# axiom_beta_sensor_cmv12000_tht_v0_16c.net
KiCad netlist of a schematic drawn in EAGLE
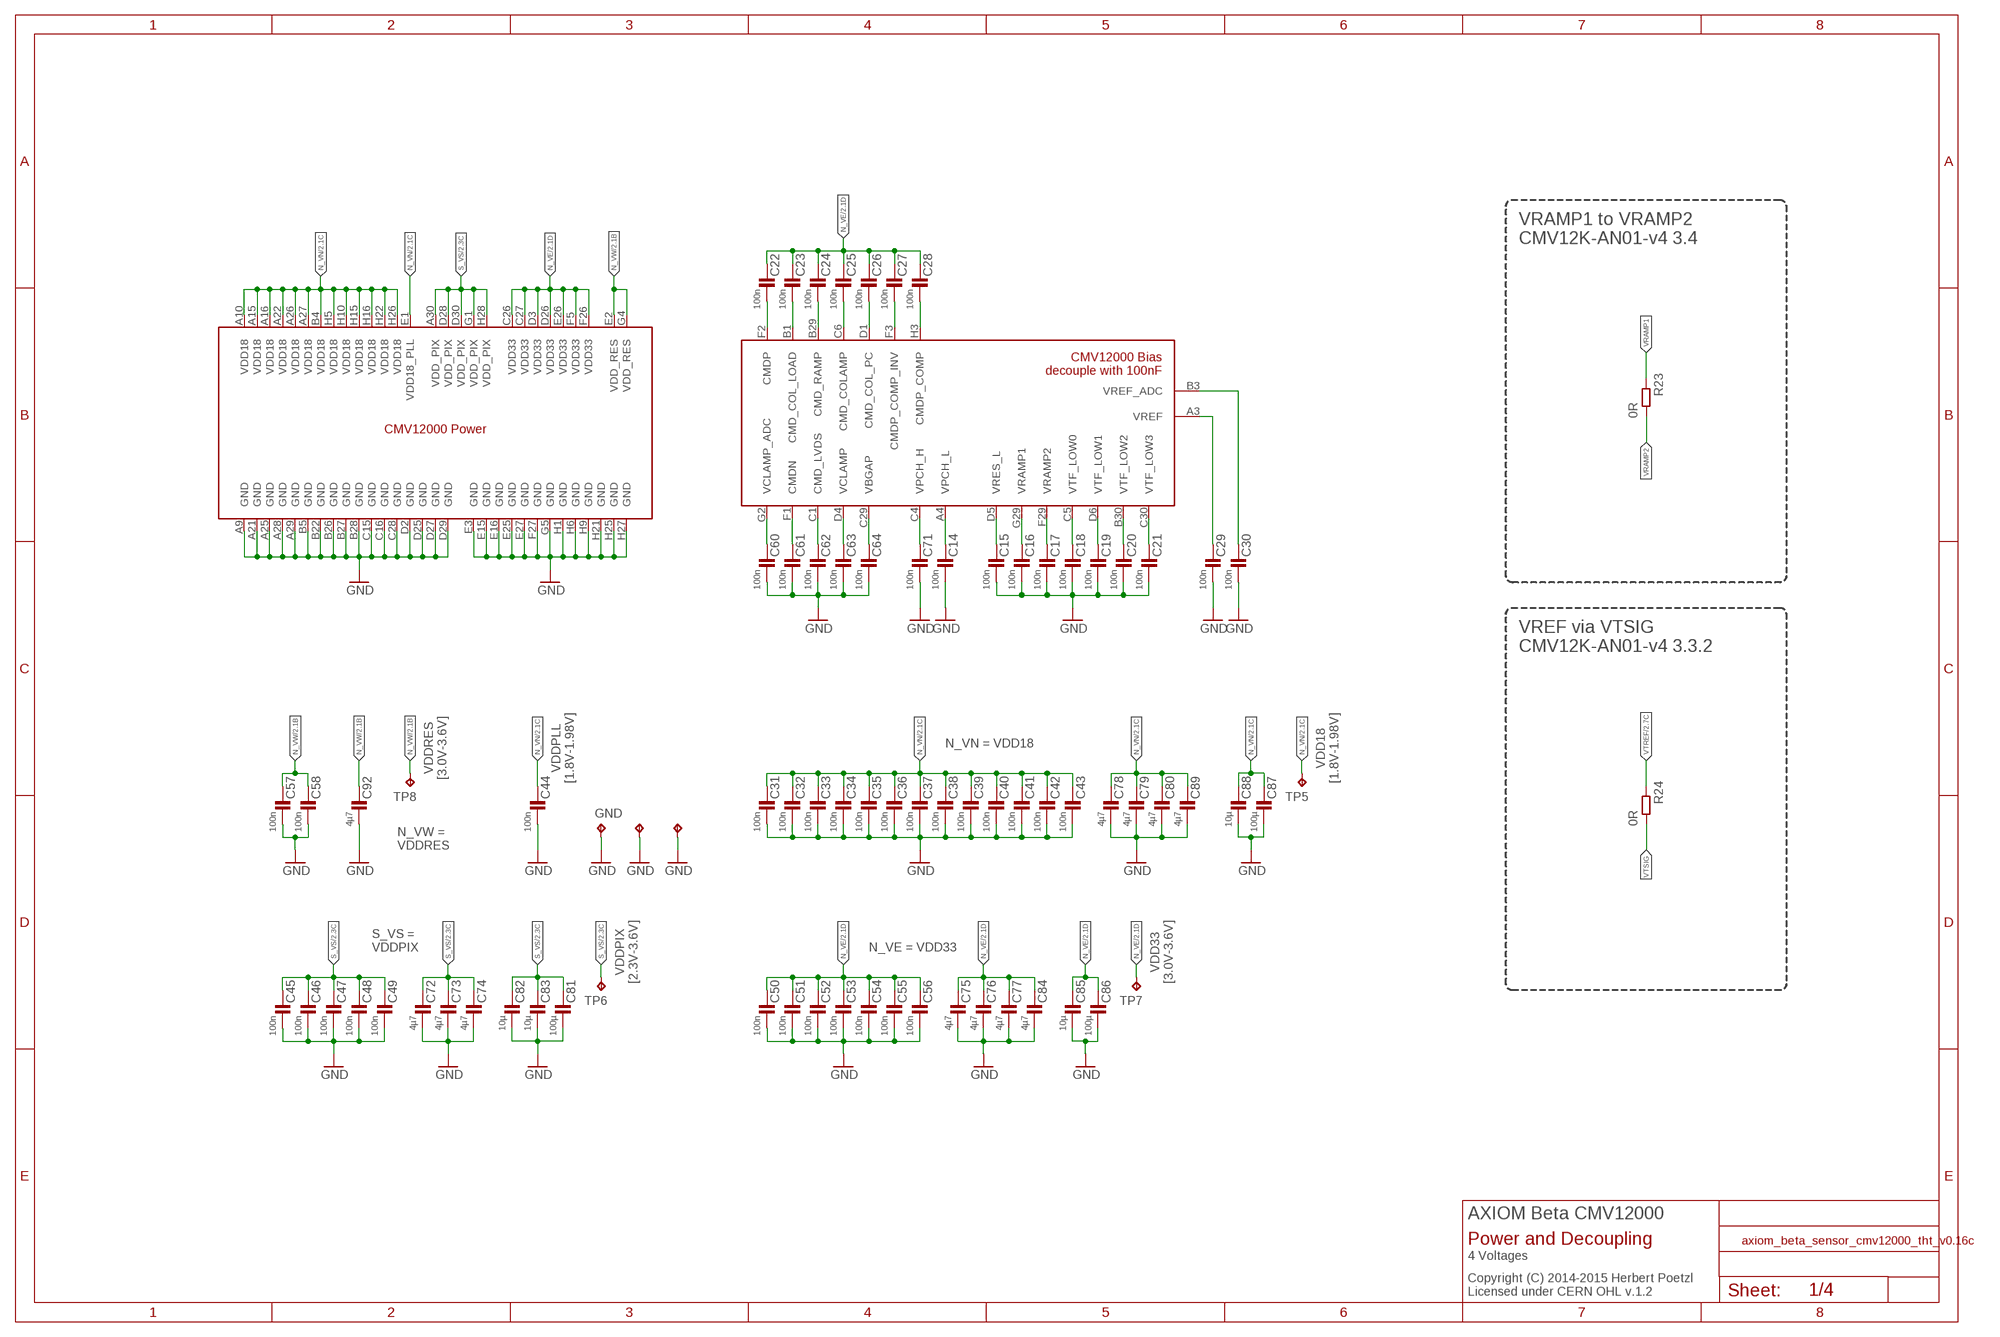
[diagram p0: schematic, sheet 1]
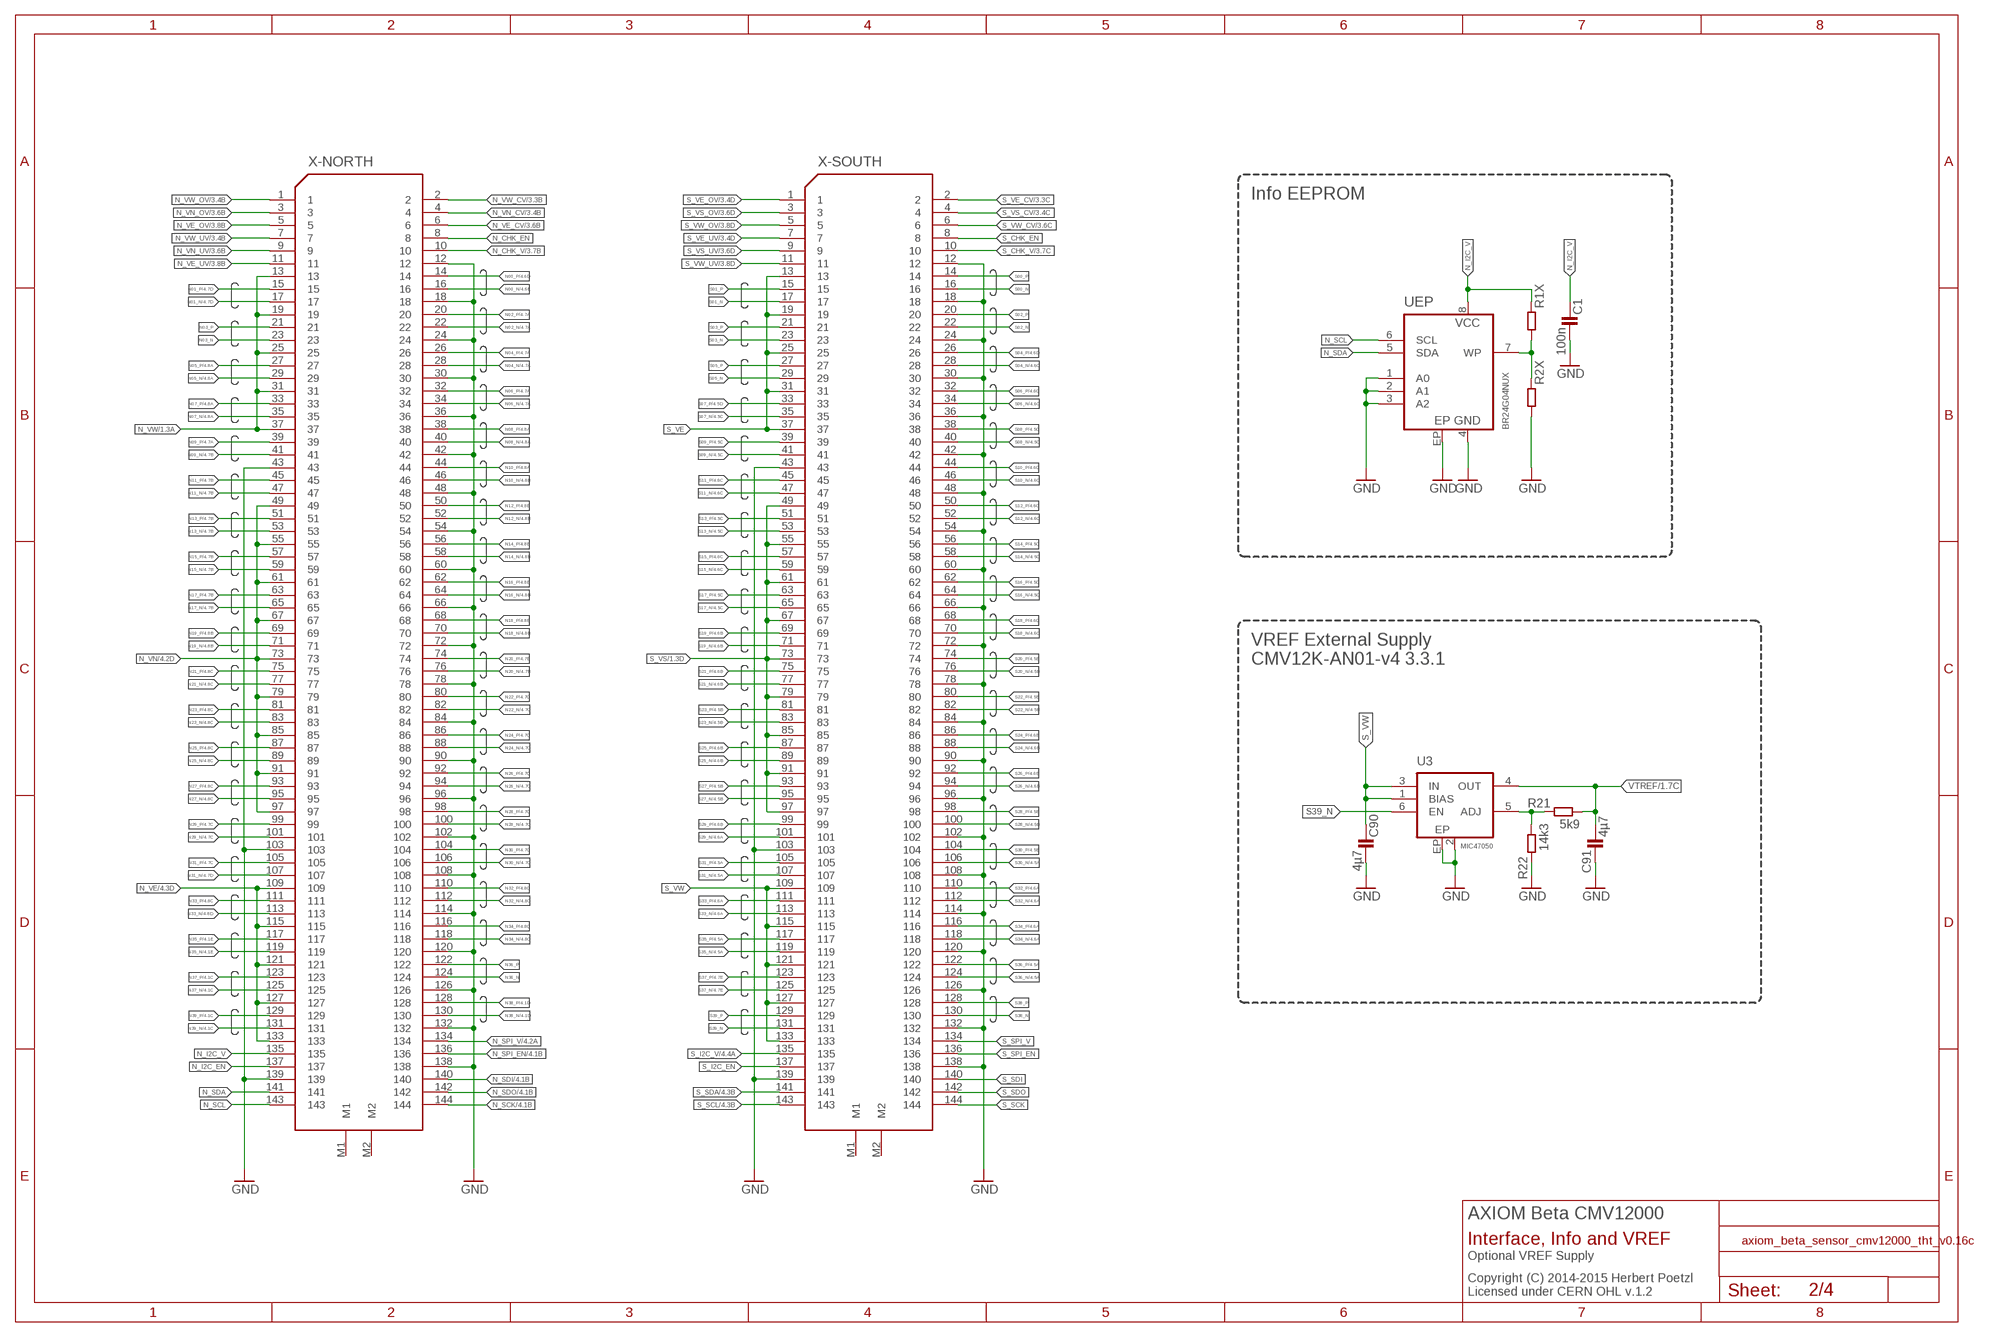
[diagram p1: schematic, sheet 2]
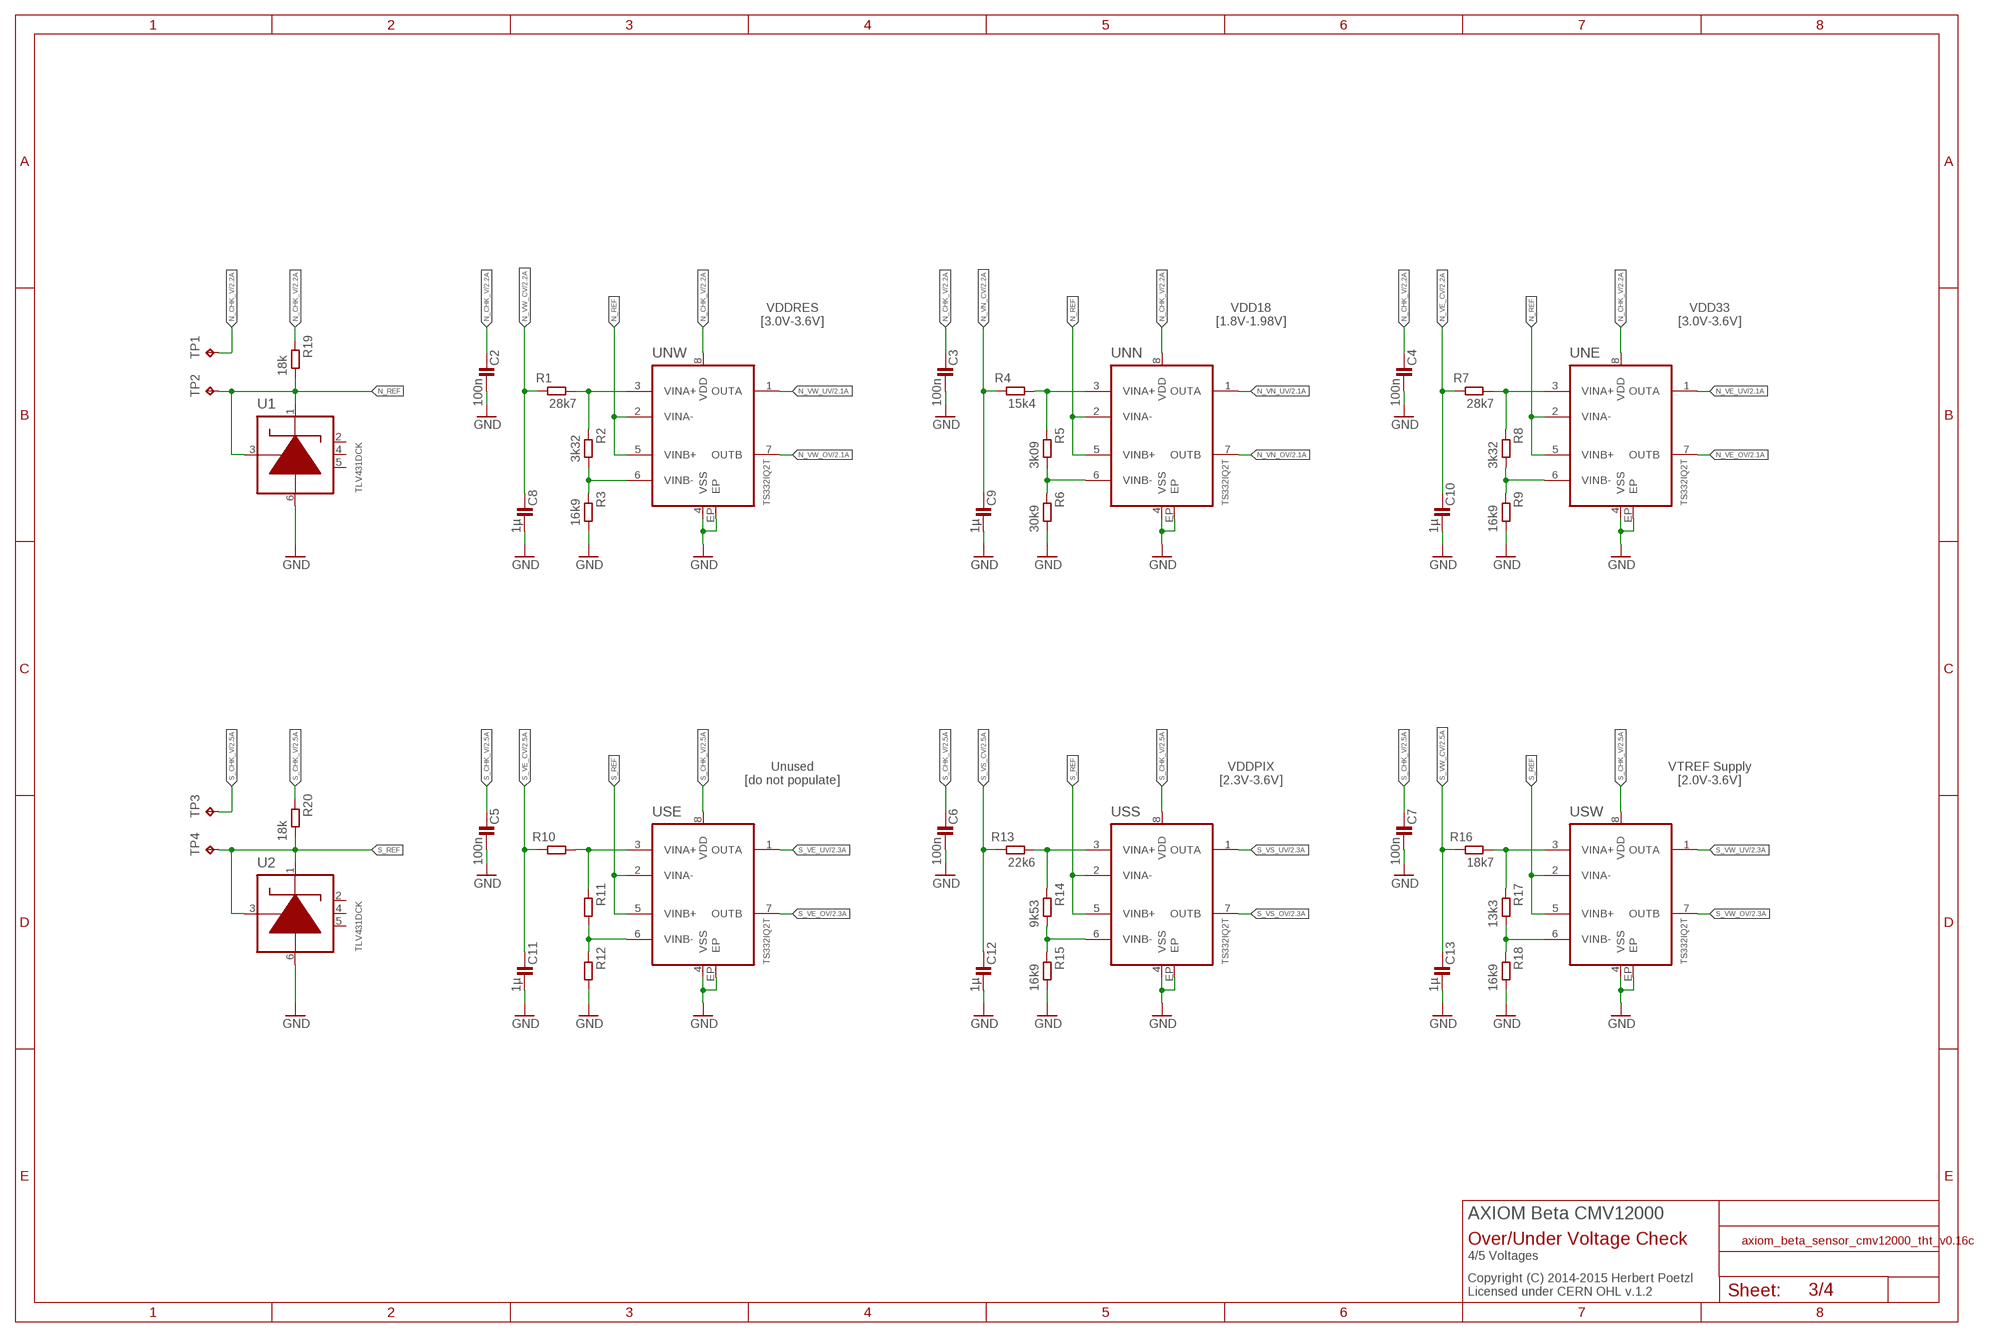
[diagram p2: schematic, sheet 3]
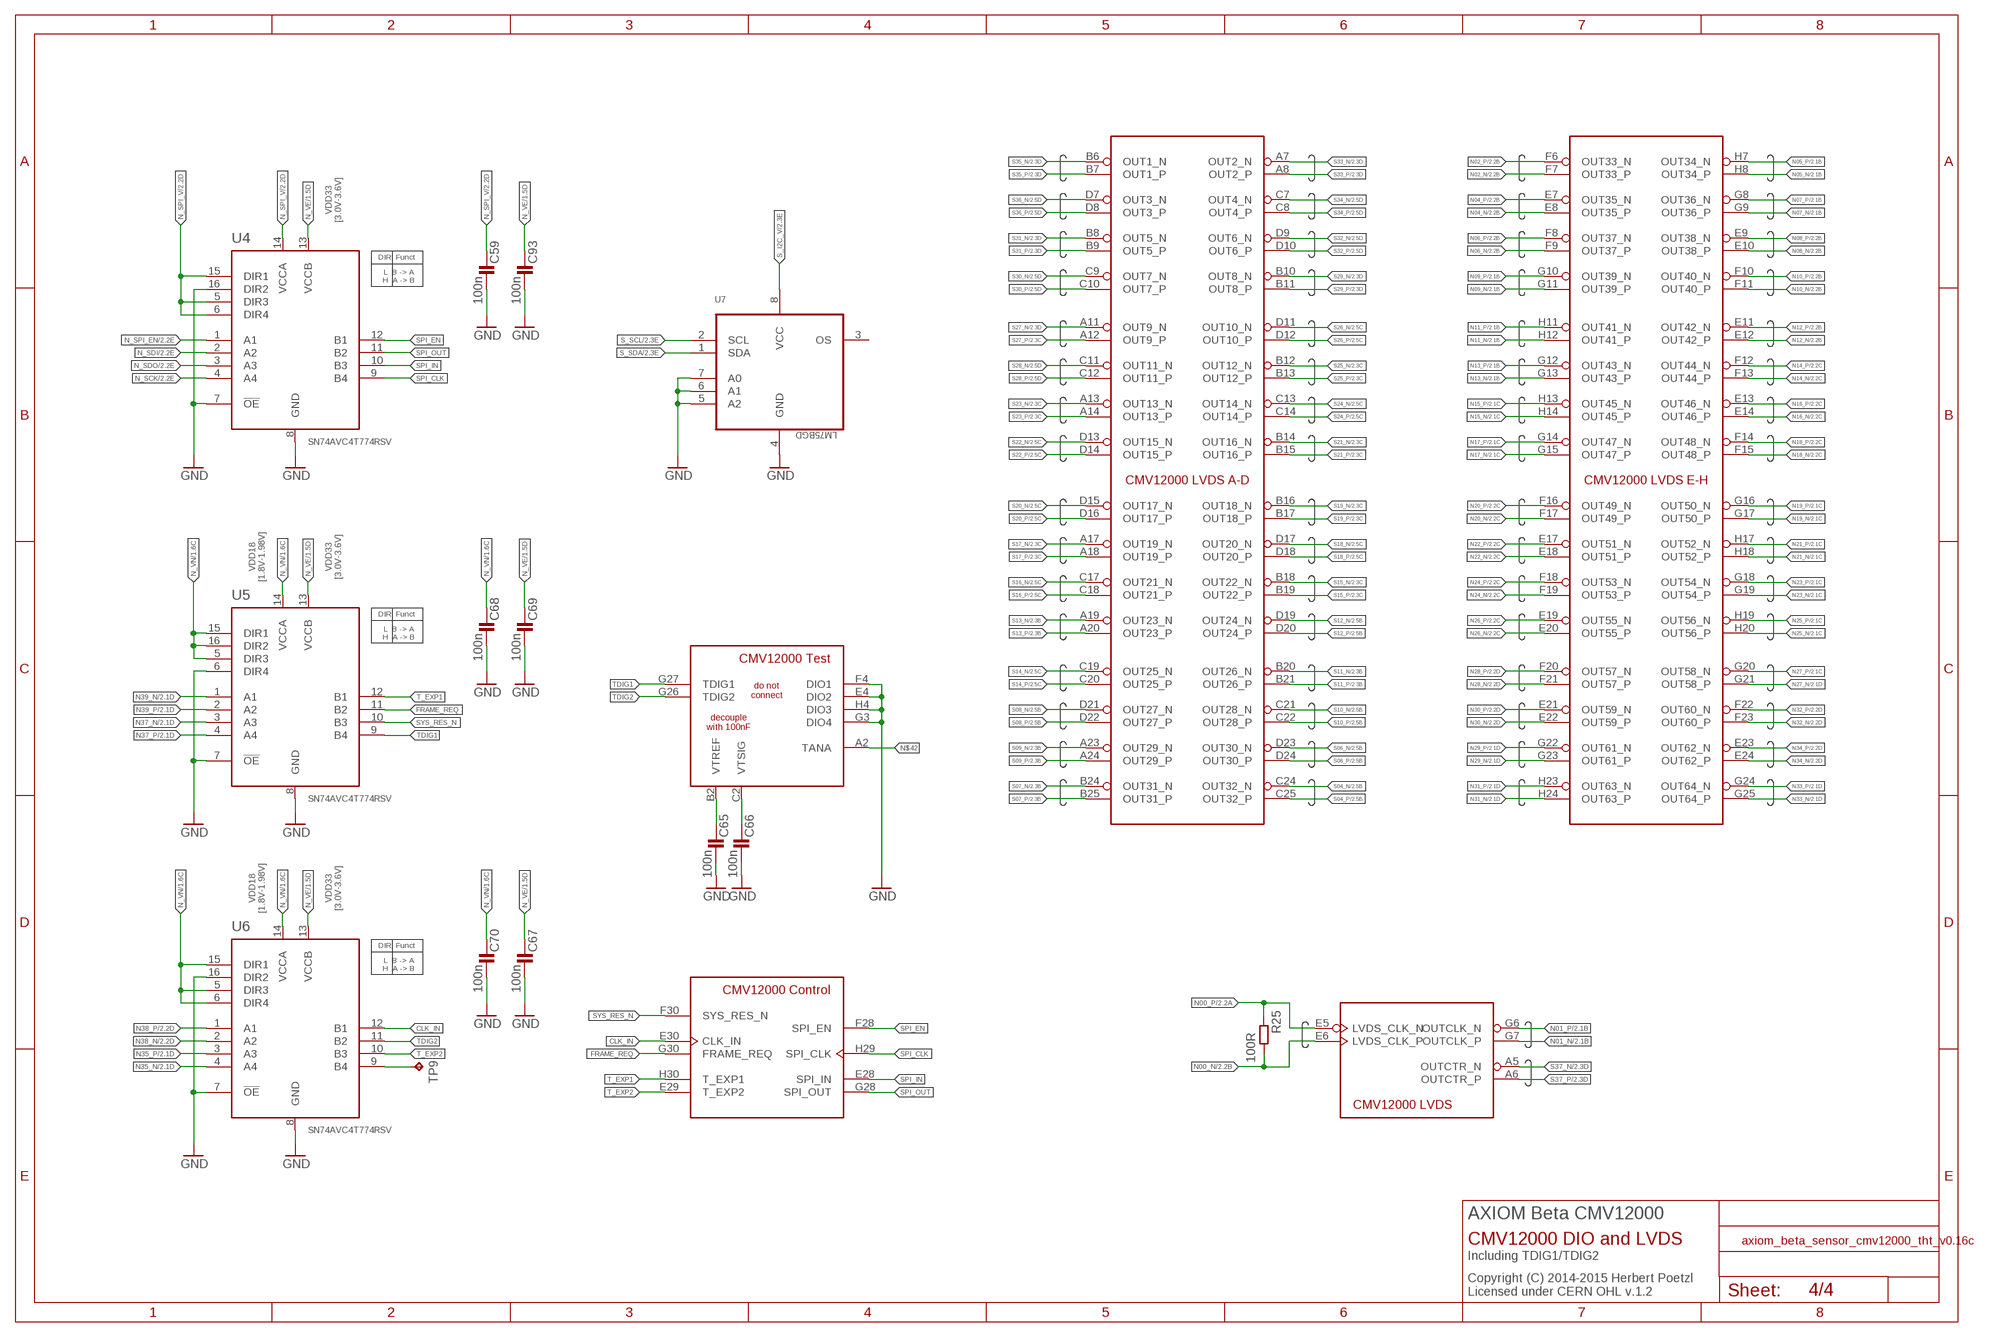
[diagram p3: schematic, sheet 4]

(export (version "E")
  (design (tool "Eeschema 10.0.6"))
  (components
    (comp (ref "C2")
      (value "100n")
      (footprint "eagle-import:0402-C")
      (libsource (lib "eagle-import") (part "C0402-C"))
    )
    (comp (ref "C3")
      (value "100n")
      (footprint "eagle-import:0402-C")
      (libsource (lib "eagle-import") (part "C0402-C"))
    )
    (comp (ref "C4")
      (value "100n")
      (footprint "eagle-import:0402-C")
      (libsource (lib "eagle-import") (part "C0402-C"))
    )
    (comp (ref "C5")
      (value "100n")
      (footprint "eagle-import:0402-C")
      (libsource (lib "eagle-import") (part "C0402-C"))
    )
    (comp (ref "C6")
      (value "100n")
      (footprint "eagle-import:0402-C")
      (libsource (lib "eagle-import") (part "C0402-C"))
    )
    (comp (ref "C7")
      (value "100n")
      (footprint "eagle-import:0402-C")
      (libsource (lib "eagle-import") (part "C0402-C"))
    )
    (comp (ref "C8")
      (value "1µ")
      (footprint "eagle-import:0402-C")
      (libsource (lib "eagle-import") (part "C0402-C"))
    )
    (comp (ref "C9")
      (value "1µ")
      (footprint "eagle-import:0402-C")
      (libsource (lib "eagle-import") (part "C0402-C"))
    )
    (comp (ref "C10")
      (value "1µ")
      (footprint "eagle-import:0402-C")
      (libsource (lib "eagle-import") (part "C0402-C"))
    )
    (comp (ref "C11")
      (value "1µ")
      (footprint "eagle-import:0402-C")
      (libsource (lib "eagle-import") (part "C0402-C"))
    )
    (comp (ref "C12")
      (value "1µ")
      (footprint "eagle-import:0402-C")
      (libsource (lib "eagle-import") (part "C0402-C"))
    )
    (comp (ref "C13")
      (value "1µ")
      (footprint "eagle-import:0402-C")
      (libsource (lib "eagle-import") (part "C0402-C"))
    )
    (comp (ref "R1")
      (value "28k7")
      (footprint "eagle-import:0402-C")
      (libsource (lib "eagle-import") (part "R0402-C"))
    )
    (comp (ref "R2")
      (value "3k32")
      (footprint "eagle-import:0402-C")
      (libsource (lib "eagle-import") (part "R0402-C"))
    )
    (comp (ref "R3")
      (value "16k9")
      (footprint "eagle-import:0402-C")
      (libsource (lib "eagle-import") (part "R0402-C"))
    )
    (comp (ref "R4")
      (value "15k4")
      (footprint "eagle-import:0402-C")
      (libsource (lib "eagle-import") (part "R0402-C"))
    )
    (comp (ref "R5")
      (value "3k09")
      (footprint "eagle-import:0402-C")
      (libsource (lib "eagle-import") (part "R0402-C"))
    )
    (comp (ref "R6")
      (value "30k9")
      (footprint "eagle-import:0402-C")
      (libsource (lib "eagle-import") (part "R0402-C"))
    )
    (comp (ref "R7")
      (value "28k7")
      (footprint "eagle-import:0402-C")
      (libsource (lib "eagle-import") (part "R0402-C"))
    )
    (comp (ref "R8")
      (value "3k32")
      (footprint "eagle-import:0402-C")
      (libsource (lib "eagle-import") (part "R0402-C"))
    )
    (comp (ref "R9")
      (value "16k9")
      (footprint "eagle-import:0402-C")
      (libsource (lib "eagle-import") (part "R0402-C"))
    )
    (comp (ref "R10")
      (value "R0402-C")
      (footprint "eagle-import:0402-C")
      (libsource (lib "eagle-import") (part "R0402-C"))
    )
    (comp (ref "R11")
      (value "R0402-C")
      (footprint "eagle-import:0402-C")
      (libsource (lib "eagle-import") (part "R0402-C"))
    )
    (comp (ref "R12")
      (value "R0402-C")
      (footprint "eagle-import:0402-C")
      (libsource (lib "eagle-import") (part "R0402-C"))
    )
    (comp (ref "R13")
      (value "22k6")
      (footprint "eagle-import:0402-C")
      (libsource (lib "eagle-import") (part "R0402-C"))
    )
    (comp (ref "R14")
      (value "9k53")
      (footprint "eagle-import:0402-C")
      (libsource (lib "eagle-import") (part "R0402-C"))
    )
    (comp (ref "R15")
      (value "16k9")
      (footprint "eagle-import:0402-C")
      (libsource (lib "eagle-import") (part "R0402-C"))
    )
    (comp (ref "R16")
      (value "18k7")
      (footprint "eagle-import:0402-C")
      (libsource (lib "eagle-import") (part "R0402-C"))
    )
    (comp (ref "R17")
      (value "13k3")
      (footprint "eagle-import:0402-C")
      (libsource (lib "eagle-import") (part "R0402-C"))
    )
    (comp (ref "R18")
      (value "16k9")
      (footprint "eagle-import:0402-C")
      (libsource (lib "eagle-import") (part "R0402-C"))
    )
    (comp (ref "R19")
      (value "18k")
      (footprint "eagle-import:0402-C")
      (libsource (lib "eagle-import") (part "R0402-C"))
    )
    (comp (ref "R20")
      (value "18k")
      (footprint "eagle-import:0402-C")
      (libsource (lib "eagle-import") (part "R0402-C"))
    )
    (comp (ref "TP1")
      (value "TPTP10R")
      (footprint "eagle-import:TP10R")
      (libsource (lib "eagle-import") (part "TPTP10R"))
    )
    (comp (ref "TP2")
      (value "TPTP10R")
      (footprint "eagle-import:TP10R")
      (libsource (lib "eagle-import") (part "TPTP10R"))
    )
    (comp (ref "TP3")
      (value "TPTP10R")
      (footprint "eagle-import:TP10R")
      (libsource (lib "eagle-import") (part "TPTP10R"))
    )
    (comp (ref "TP4")
      (value "TPTP10R")
      (footprint "eagle-import:TP10R")
      (libsource (lib "eagle-import") (part "TPTP10R"))
    )
    (comp (ref "U1")
      (value "TLV431DCK")
      (footprint "eagle-import:SOT65P210X110-6N")
      (libsource (lib "eagle-import") (part "TLV431DCK"))
    )
    (comp (ref "U2")
      (value "TLV431DCK")
      (footprint "eagle-import:SOT65P210X110-6N")
      (libsource (lib "eagle-import") (part "TLV431DCK"))
    )
    (comp (ref "UNE")
      (value "TS332IQ2T")
      (footprint "eagle-import:DFN200X200X100-9N")
      (libsource (lib "eagle-import") (part "TS332IQ2T"))
    )
    (comp (ref "UNN")
      (value "TS332IQ2T")
      (footprint "eagle-import:DFN200X200X100-9N")
      (libsource (lib "eagle-import") (part "TS332IQ2T"))
    )
    (comp (ref "UNW")
      (value "TS332IQ2T")
      (footprint "eagle-import:DFN200X200X100-9N")
      (libsource (lib "eagle-import") (part "TS332IQ2T"))
    )
    (comp (ref "USE")
      (value "TS332IQ2T")
      (footprint "eagle-import:DFN200X200X100-9N")
      (libsource (lib "eagle-import") (part "TS332IQ2T"))
    )
    (comp (ref "USS")
      (value "TS332IQ2T")
      (footprint "eagle-import:DFN200X200X100-9N")
      (libsource (lib "eagle-import") (part "TS332IQ2T"))
    )
    (comp (ref "USW")
      (value "TS332IQ2T")
      (footprint "eagle-import:DFN200X200X100-9N")
      (libsource (lib "eagle-import") (part "TS332IQ2T"))
    )
    (comp (ref "C1")
      (value "100n")
      (footprint "eagle-import:0402-C")
      (libsource (lib "eagle-import") (part "C0402-C"))
    )
    (comp (ref "C90")
      (value "4µ7")
      (footprint "eagle-import:0402-C")
      (libsource (lib "eagle-import") (part "C0402-C"))
    )
    (comp (ref "C91")
      (value "4µ7")
      (footprint "eagle-import:0402-C")
      (libsource (lib "eagle-import") (part "C0402-C"))
    )
    (comp (ref "R1X")
      (value "R0402-C")
      (footprint "eagle-import:0402-C")
      (libsource (lib "eagle-import") (part "R0402-C"))
    )
    (comp (ref "R2X")
      (value "R0402-C")
      (footprint "eagle-import:0402-C")
      (libsource (lib "eagle-import") (part "R0402-C"))
    )
    (comp (ref "R21")
      (value "5k9")
      (footprint "eagle-import:0402-C")
      (libsource (lib "eagle-import") (part "R0402-C"))
    )
    (comp (ref "R22")
      (value "14k3")
      (footprint "eagle-import:0402-C")
      (libsource (lib "eagle-import") (part "R0402-C"))
    )
    (comp (ref "U3")
      (value "MIC47050")
      (footprint "eagle-import:MLF-6")
      (libsource (lib "eagle-import") (part "MIC47050-ADJ"))
    )
    (comp (ref "UEP")
      (value "BR24G04NUX")
      (footprint "eagle-import:DFN200X300X100-9N")
      (libsource (lib "eagle-import") (part "BR24G04NUX"))
    )
    (comp (ref "X-NORTH")
      (value "FX10-144P")
      (footprint "eagle-import:FX10A-144P")
      (libsource (lib "eagle-import") (part "FX10-144P"))
    )
    (comp (ref "X-SOUTH")
      (value "FX10-144P")
      (footprint "eagle-import:FX10A-144P")
      (libsource (lib "eagle-import") (part "FX10-144P"))
    )
    (comp (ref "C14")
      (value "100n")
      (footprint "eagle-import:0402-C")
      (libsource (lib "eagle-import") (part "C0402-C"))
    )
    (comp (ref "C15")
      (value "100n")
      (footprint "eagle-import:0402-C")
      (libsource (lib "eagle-import") (part "C0402-C"))
    )
    (comp (ref "C16")
      (value "100n")
      (footprint "eagle-import:0402-C")
      (libsource (lib "eagle-import") (part "C0402-C"))
    )
    (comp (ref "C17")
      (value "100n")
      (footprint "eagle-import:0402-C")
      (libsource (lib "eagle-import") (part "C0402-C"))
    )
    (comp (ref "C18")
      (value "100n")
      (footprint "eagle-import:0402-C")
      (libsource (lib "eagle-import") (part "C0402-C"))
    )
    (comp (ref "C19")
      (value "100n")
      (footprint "eagle-import:0402-C")
      (libsource (lib "eagle-import") (part "C0402-C"))
    )
    (comp (ref "C20")
      (value "100n")
      (footprint "eagle-import:0402-C")
      (libsource (lib "eagle-import") (part "C0402-C"))
    )
    (comp (ref "C21")
      (value "100n")
      (footprint "eagle-import:0402-C")
      (libsource (lib "eagle-import") (part "C0402-C"))
    )
    (comp (ref "C22")
      (value "100n")
      (footprint "eagle-import:0402-C")
      (libsource (lib "eagle-import") (part "C0402-C"))
    )
    (comp (ref "C23")
      (value "100n")
      (footprint "eagle-import:0402-C")
      (libsource (lib "eagle-import") (part "C0402-C"))
    )
    (comp (ref "C24")
      (value "100n")
      (footprint "eagle-import:0402-C")
      (libsource (lib "eagle-import") (part "C0402-C"))
    )
    (comp (ref "C25")
      (value "100n")
      (footprint "eagle-import:0402-C")
      (libsource (lib "eagle-import") (part "C0402-C"))
    )
    (comp (ref "C26")
      (value "100n")
      (footprint "eagle-import:0402-C")
      (libsource (lib "eagle-import") (part "C0402-C"))
    )
    (comp (ref "C27")
      (value "100n")
      (footprint "eagle-import:0402-C")
      (libsource (lib "eagle-import") (part "C0402-C"))
    )
    (comp (ref "C28")
      (value "100n")
      (footprint "eagle-import:0402-C")
      (libsource (lib "eagle-import") (part "C0402-C"))
    )
    (comp (ref "C29")
      (value "100n")
      (footprint "eagle-import:0402-C")
      (libsource (lib "eagle-import") (part "C0402-C"))
    )
    (comp (ref "C30")
      (value "100n")
      (footprint "eagle-import:0402-C")
      (libsource (lib "eagle-import") (part "C0402-C"))
    )
    (comp (ref "C31")
      (value "100n")
      (footprint "eagle-import:0402-C")
      (libsource (lib "eagle-import") (part "C0402-C"))
    )
    (comp (ref "C32")
      (value "100n")
      (footprint "eagle-import:0402-C")
      (libsource (lib "eagle-import") (part "C0402-C"))
    )
    (comp (ref "C33")
      (value "100n")
      (footprint "eagle-import:0402-C")
      (libsource (lib "eagle-import") (part "C0402-C"))
    )
    (comp (ref "C34")
      (value "100n")
      (footprint "eagle-import:0402-C")
      (libsource (lib "eagle-import") (part "C0402-C"))
    )
    (comp (ref "C35")
      (value "100n")
      (footprint "eagle-import:0402-C")
      (libsource (lib "eagle-import") (part "C0402-C"))
    )
    (comp (ref "C36")
      (value "100n")
      (footprint "eagle-import:0402-C")
      (libsource (lib "eagle-import") (part "C0402-C"))
    )
    (comp (ref "C37")
      (value "100n")
      (footprint "eagle-import:0402-C")
      (libsource (lib "eagle-import") (part "C0402-C"))
    )
    (comp (ref "C38")
      (value "100n")
      (footprint "eagle-import:0402-C")
      (libsource (lib "eagle-import") (part "C0402-C"))
    )
    (comp (ref "C39")
      (value "100n")
      (footprint "eagle-import:0402-C")
      (libsource (lib "eagle-import") (part "C0402-C"))
    )
    (comp (ref "C40")
      (value "100n")
      (footprint "eagle-import:0402-C")
      (libsource (lib "eagle-import") (part "C0402-C"))
    )
    (comp (ref "C41")
      (value "100n")
      (footprint "eagle-import:0402-C")
      (libsource (lib "eagle-import") (part "C0402-C"))
    )
    (comp (ref "C42")
      (value "100n")
      (footprint "eagle-import:0402-C")
      (libsource (lib "eagle-import") (part "C0402-C"))
    )
    (comp (ref "C43")
      (value "100n")
      (footprint "eagle-import:0402-C")
      (libsource (lib "eagle-import") (part "C0402-C"))
    )
    (comp (ref "C44")
      (value "100n")
      (footprint "eagle-import:0402-C")
      (libsource (lib "eagle-import") (part "C0402-C"))
    )
    (comp (ref "C45")
      (value "100n")
      (footprint "eagle-import:0402-C")
      (libsource (lib "eagle-import") (part "C0402-C"))
    )
    (comp (ref "C46")
      (value "100n")
      (footprint "eagle-import:0402-C")
      (libsource (lib "eagle-import") (part "C0402-C"))
    )
    (comp (ref "C47")
      (value "100n")
      (footprint "eagle-import:0402-C")
      (libsource (lib "eagle-import") (part "C0402-C"))
    )
    (comp (ref "C48")
      (value "100n")
      (footprint "eagle-import:0402-C")
      (libsource (lib "eagle-import") (part "C0402-C"))
    )
    (comp (ref "C49")
      (value "100n")
      (footprint "eagle-import:0402-C")
      (libsource (lib "eagle-import") (part "C0402-C"))
    )
    (comp (ref "C50")
      (value "100n")
      (footprint "eagle-import:0402-C")
      (libsource (lib "eagle-import") (part "C0402-C"))
    )
    (comp (ref "C51")
      (value "100n")
      (footprint "eagle-import:0402-C")
      (libsource (lib "eagle-import") (part "C0402-C"))
    )
    (comp (ref "C52")
      (value "100n")
      (footprint "eagle-import:0402-C")
      (libsource (lib "eagle-import") (part "C0402-C"))
    )
    (comp (ref "C53")
      (value "100n")
      (footprint "eagle-import:0402-C")
      (libsource (lib "eagle-import") (part "C0402-C"))
    )
    (comp (ref "C54")
      (value "100n")
      (footprint "eagle-import:0402-C")
      (libsource (lib "eagle-import") (part "C0402-C"))
    )
    (comp (ref "C55")
      (value "100n")
      (footprint "eagle-import:0402-C")
      (libsource (lib "eagle-import") (part "C0402-C"))
    )
    (comp (ref "C56")
      (value "100n")
      (footprint "eagle-import:0402-C")
      (libsource (lib "eagle-import") (part "C0402-C"))
    )
    (comp (ref "C57")
      (value "100n")
      (footprint "eagle-import:0402-C")
      (libsource (lib "eagle-import") (part "C0402-C"))
    )
    (comp (ref "C58")
      (value "100n")
      (footprint "eagle-import:0402-C")
      (libsource (lib "eagle-import") (part "C0402-C"))
    )
    (comp (ref "C60")
      (value "100n")
      (footprint "eagle-import:0402-C")
      (libsource (lib "eagle-import") (part "C0402-C"))
    )
    (comp (ref "C61")
      (value "100n")
      (footprint "eagle-import:0402-C")
      (libsource (lib "eagle-import") (part "C0402-C"))
    )
    (comp (ref "C62")
      (value "100n")
      (footprint "eagle-import:0402-C")
      (libsource (lib "eagle-import") (part "C0402-C"))
    )
    (comp (ref "C63")
      (value "100n")
      (footprint "eagle-import:0402-C")
      (libsource (lib "eagle-import") (part "C0402-C"))
    )
    (comp (ref "C64")
      (value "100n")
      (footprint "eagle-import:0402-C")
      (libsource (lib "eagle-import") (part "C0402-C"))
    )
    (comp (ref "C71")
      (value "100n")
      (footprint "eagle-import:0402-C")
      (libsource (lib "eagle-import") (part "C0402-C"))
    )
    (comp (ref "C72")
      (value "4µ7")
      (footprint "eagle-import:0402-B")
      (libsource (lib "eagle-import") (part "C0402-B"))
    )
    (comp (ref "C73")
      (value "4µ7")
      (footprint "eagle-import:0402-C")
      (libsource (lib "eagle-import") (part "C0402-C"))
    )
    (comp (ref "C74")
      (value "4µ7")
      (footprint "eagle-import:0402-C")
      (libsource (lib "eagle-import") (part "C0402-C"))
    )
    (comp (ref "C75")
      (value "4µ7")
      (footprint "eagle-import:0402-C")
      (libsource (lib "eagle-import") (part "C0402-C"))
    )
    (comp (ref "C76")
      (value "4µ7")
      (footprint "eagle-import:0402-C")
      (libsource (lib "eagle-import") (part "C0402-C"))
    )
    (comp (ref "C77")
      (value "4µ7")
      (footprint "eagle-import:0402-B")
      (libsource (lib "eagle-import") (part "C0402-B"))
    )
    (comp (ref "C78")
      (value "4µ7")
      (footprint "eagle-import:0402-B")
      (libsource (lib "eagle-import") (part "C0402-B"))
    )
    (comp (ref "C79")
      (value "4µ7")
      (footprint "eagle-import:0402-C")
      (libsource (lib "eagle-import") (part "C0402-C"))
    )
    (comp (ref "C80")
      (value "4µ7")
      (footprint "eagle-import:0402-C")
      (libsource (lib "eagle-import") (part "C0402-C"))
    )
    (comp (ref "C81")
      (value "100µ")
      (footprint "eagle-import:1206-B")
      (libsource (lib "eagle-import") (part "C1206-B"))
    )
    (comp (ref "C82")
      (value "10µ")
      (footprint "eagle-import:0603-C")
      (libsource (lib "eagle-import") (part "C0603-C"))
    )
    (comp (ref "C83")
      (value "10µ")
      (footprint "eagle-import:0603-C")
      (libsource (lib "eagle-import") (part "C0603-C"))
    )
    (comp (ref "C84")
      (value "4µ7")
      (footprint "eagle-import:0402-C")
      (libsource (lib "eagle-import") (part "C0402-C"))
    )
    (comp (ref "C85")
      (value "10µ")
      (footprint "eagle-import:0603-C")
      (libsource (lib "eagle-import") (part "C0603-C"))
    )
    (comp (ref "C86")
      (value "100µ")
      (footprint "eagle-import:1206-B")
      (libsource (lib "eagle-import") (part "C1206-B"))
    )
    (comp (ref "C87")
      (value "100µ")
      (footprint "eagle-import:1206-B")
      (libsource (lib "eagle-import") (part "C1206-B"))
    )
    (comp (ref "C88")
      (value "10µ")
      (footprint "eagle-import:0603-C")
      (libsource (lib "eagle-import") (part "C0603-C"))
    )
    (comp (ref "C89")
      (value "4µ7")
      (footprint "eagle-import:0402-C")
      (libsource (lib "eagle-import") (part "C0402-C"))
    )
    (comp (ref "C92")
      (value "4µ7")
      (footprint "eagle-import:0402-C")
      (libsource (lib "eagle-import") (part "C0402-C"))
    )
    (comp (ref "GND")
      (value "TPTP10R")
      (footprint "eagle-import:TP10R")
      (libsource (lib "eagle-import") (part "TPTP10R"))
    )
    (comp (ref "GND75")
      (value "TPTP10R")
      (footprint "eagle-import:TP10R")
      (libsource (lib "eagle-import") (part "TPTP10R"))
    )
    (comp (ref "GND77")
      (value "TPTP10R")
      (footprint "eagle-import:TP10R")
      (libsource (lib "eagle-import") (part "TPTP10R"))
    )
    (comp (ref "R23")
      (value "0R")
      (footprint "eagle-import:0402-C")
      (libsource (lib "eagle-import") (part "R0402-C"))
    )
    (comp (ref "R24")
      (value "0R")
      (footprint "eagle-import:0402-C")
      (libsource (lib "eagle-import") (part "R0402-C"))
    )
    (comp (ref "SENSOR")
      (value "CMV12000ANDON")
      (footprint "eagle-import:10-30-07-237-400T4")
      (libsource (lib "eagle-import") (part "CMV12000ANDON"))
    )
    (comp (ref "TP5")
      (value "TPTP10R")
      (footprint "eagle-import:TP10R")
      (libsource (lib "eagle-import") (part "TPTP10R"))
    )
    (comp (ref "TP6")
      (value "TPTP10R")
      (footprint "eagle-import:TP10R")
      (libsource (lib "eagle-import") (part "TPTP10R"))
    )
    (comp (ref "TP7")
      (value "TPTP10R")
      (footprint "eagle-import:TP10R")
      (libsource (lib "eagle-import") (part "TPTP10R"))
    )
    (comp (ref "TP8")
      (value "TPTP10R")
      (footprint "eagle-import:TP10R")
      (libsource (lib "eagle-import") (part "TPTP10R"))
    )
    (comp (ref "C59")
      (value "100n")
      (footprint "eagle-import:0402-C")
      (libsource (lib "eagle-import") (part "C0402-C"))
    )
    (comp (ref "C65")
      (value "100n")
      (footprint "eagle-import:0402-C")
      (libsource (lib "eagle-import") (part "C0402-C"))
    )
    (comp (ref "C66")
      (value "100n")
      (footprint "eagle-import:0402-C")
      (libsource (lib "eagle-import") (part "C0402-C"))
    )
    (comp (ref "C67")
      (value "100n")
      (footprint "eagle-import:0402-C")
      (libsource (lib "eagle-import") (part "C0402-C"))
    )
    (comp (ref "C68")
      (value "100n")
      (footprint "eagle-import:0402-C")
      (libsource (lib "eagle-import") (part "C0402-C"))
    )
    (comp (ref "C69")
      (value "100n")
      (footprint "eagle-import:0402-C")
      (libsource (lib "eagle-import") (part "C0402-C"))
    )
    (comp (ref "C70")
      (value "100n")
      (footprint "eagle-import:0402-C")
      (libsource (lib "eagle-import") (part "C0402-C"))
    )
    (comp (ref "C93")
      (value "100n")
      (footprint "eagle-import:0402-C")
      (libsource (lib "eagle-import") (part "C0402-C"))
    )
    (comp (ref "R25")
      (value "100R")
      (footprint "eagle-import:0402-C")
      (libsource (lib "eagle-import") (part "R0402-C"))
    )
    (comp (ref "TP9")
      (value "TPTP10R")
      (footprint "eagle-import:TP10R")
      (libsource (lib "eagle-import") (part "TPTP10R"))
    )
    (comp (ref "U4")
      (value "SN74AVC4T774RSV")
      (footprint "eagle-import:QFN40P185X265X55-16N")
      (libsource (lib "eagle-import") (part "SN74AVC4T774RSV"))
    )
    (comp (ref "U5")
      (value "SN74AVC4T774RSV")
      (footprint "eagle-import:QFN40P185X265X55-16N")
      (libsource (lib "eagle-import") (part "SN74AVC4T774RSV"))
    )
    (comp (ref "U6")
      (value "SN74AVC4T774RSV")
      (footprint "eagle-import:QFN40P185X265X55-16N")
      (libsource (lib "eagle-import") (part "SN74AVC4T774RSV"))
    )
    (comp (ref "U7")
      (value "LM75BGD")
      (footprint "eagle-import:SOT996-2_3")
      (libsource (lib "eagle-import") (part "LM75BGD"))
    )
  )
  (nets
    (net (code "1") (name "CLK_IN") (class "Default")
      (node (ref "SENSOR") (pin "E30") (pinfunction "CLK_IN_E30") (pintype "input"))
      (node (ref "U6") (pin "12") (pinfunction "B1_12") (pintype "bidirectional"))
    )
    (net (code "2") (name "FRAME_REQ") (class "Default")
      (node (ref "SENSOR") (pin "G30") (pinfunction "FRAME_REQ_G30") (pintype "input"))
      (node (ref "U5") (pin "11") (pinfunction "B2_11") (pintype "bidirectional"))
    )
    (net (code "3") (name "GND") (class "Default")
      (node (ref "C1") (pin "2") (pinfunction "2_2") (pintype "passive"))
      (node (ref "C10") (pin "2") (pinfunction "2_2") (pintype "passive"))
      (node (ref "C11") (pin "2") (pinfunction "2_2") (pintype "passive"))
      (node (ref "C12") (pin "2") (pinfunction "2_2") (pintype "passive"))
      (node (ref "C13") (pin "2") (pinfunction "2_2") (pintype "passive"))
      (node (ref "C14") (pin "2") (pinfunction "2_2") (pintype "passive"))
      (node (ref "C15") (pin "2") (pinfunction "2_2") (pintype "passive"))
      (node (ref "C16") (pin "2") (pinfunction "2_2") (pintype "passive"))
      (node (ref "C17") (pin "2") (pinfunction "2_2") (pintype "passive"))
      (node (ref "C18") (pin "2") (pinfunction "2_2") (pintype "passive"))
      (node (ref "C19") (pin "2") (pinfunction "2_2") (pintype "passive"))
      (node (ref "C2") (pin "2") (pinfunction "2_2") (pintype "passive"))
      (node (ref "C20") (pin "2") (pinfunction "2_2") (pintype "passive"))
      (node (ref "C21") (pin "2") (pinfunction "2_2") (pintype "passive"))
      (node (ref "C29") (pin "2") (pinfunction "2_2") (pintype "passive"))
      (node (ref "C3") (pin "2") (pinfunction "2_2") (pintype "passive"))
      (node (ref "C30") (pin "2") (pinfunction "2_2") (pintype "passive"))
      (node (ref "C31") (pin "2") (pinfunction "2_2") (pintype "passive"))
      (node (ref "C32") (pin "2") (pinfunction "2_2") (pintype "passive"))
      (node (ref "C33") (pin "2") (pinfunction "2_2") (pintype "passive"))
      (node (ref "C34") (pin "2") (pinfunction "2_2") (pintype "passive"))
      (node (ref "C35") (pin "2") (pinfunction "2_2") (pintype "passive"))
      (node (ref "C36") (pin "2") (pinfunction "2_2") (pintype "passive"))
      (node (ref "C37") (pin "2") (pinfunction "2_2") (pintype "passive"))
      (node (ref "C38") (pin "2") (pinfunction "2_2") (pintype "passive"))
      (node (ref "C39") (pin "2") (pinfunction "2_2") (pintype "passive"))
      (node (ref "C4") (pin "2") (pinfunction "2_2") (pintype "passive"))
      (node (ref "C40") (pin "2") (pinfunction "2_2") (pintype "passive"))
      (node (ref "C41") (pin "2") (pinfunction "2_2") (pintype "passive"))
      (node (ref "C42") (pin "2") (pinfunction "2_2") (pintype "passive"))
      (node (ref "C43") (pin "2") (pinfunction "2_2") (pintype "passive"))
      (node (ref "C44") (pin "2") (pinfunction "2_2") (pintype "passive"))
      (node (ref "C45") (pin "2") (pinfunction "2_2") (pintype "passive"))
      (node (ref "C46") (pin "2") (pinfunction "2_2") (pintype "passive"))
      (node (ref "C47") (pin "2") (pinfunction "2_2") (pintype "passive"))
      (node (ref "C48") (pin "2") (pinfunction "2_2") (pintype "passive"))
      (node (ref "C49") (pin "2") (pinfunction "2_2") (pintype "passive"))
      (node (ref "C5") (pin "2") (pinfunction "2_2") (pintype "passive"))
      (node (ref "C50") (pin "2") (pinfunction "2_2") (pintype "passive"))
      (node (ref "C51") (pin "2") (pinfunction "2_2") (pintype "passive"))
      (node (ref "C52") (pin "2") (pinfunction "2_2") (pintype "passive"))
      (node (ref "C53") (pin "2") (pinfunction "2_2") (pintype "passive"))
      (node (ref "C54") (pin "2") (pinfunction "2_2") (pintype "passive"))
      (node (ref "C55") (pin "2") (pinfunction "2_2") (pintype "passive"))
      (node (ref "C56") (pin "2") (pinfunction "2_2") (pintype "passive"))
      (node (ref "C57") (pin "2") (pinfunction "2_2") (pintype "passive"))
      (node (ref "C58") (pin "2") (pinfunction "2_2") (pintype "passive"))
      (node (ref "C59") (pin "2") (pinfunction "2_2") (pintype "passive"))
      (node (ref "C6") (pin "2") (pinfunction "2_2") (pintype "passive"))
      (node (ref "C60") (pin "2") (pinfunction "2_2") (pintype "passive"))
      (node (ref "C61") (pin "2") (pinfunction "2_2") (pintype "passive"))
      (node (ref "C62") (pin "2") (pinfunction "2_2") (pintype "passive"))
      (node (ref "C63") (pin "2") (pinfunction "2_2") (pintype "passive"))
      (node (ref "C64") (pin "2") (pinfunction "2_2") (pintype "passive"))
      (node (ref "C65") (pin "2") (pinfunction "2_2") (pintype "passive"))
      (node (ref "C66") (pin "2") (pinfunction "2_2") (pintype "passive"))
      (node (ref "C67") (pin "2") (pinfunction "2_2") (pintype "passive"))
      (node (ref "C68") (pin "2") (pinfunction "2_2") (pintype "passive"))
      (node (ref "C69") (pin "2") (pinfunction "2_2") (pintype "passive"))
      (node (ref "C7") (pin "2") (pinfunction "2_2") (pintype "passive"))
      (node (ref "C70") (pin "2") (pinfunction "2_2") (pintype "passive"))
      (node (ref "C71") (pin "2") (pinfunction "2_2") (pintype "passive"))
      (node (ref "C72") (pin "2") (pinfunction "2_2") (pintype "passive"))
      (node (ref "C73") (pin "2") (pinfunction "2_2") (pintype "passive"))
      (node (ref "C74") (pin "2") (pinfunction "2_2") (pintype "passive"))
      (node (ref "C75") (pin "2") (pinfunction "2_2") (pintype "passive"))
      (node (ref "C76") (pin "2") (pinfunction "2_2") (pintype "passive"))
      (node (ref "C77") (pin "2") (pinfunction "2_2") (pintype "passive"))
      (node (ref "C78") (pin "2") (pinfunction "2_2") (pintype "passive"))
      (node (ref "C79") (pin "2") (pinfunction "2_2") (pintype "passive"))
      (node (ref "C8") (pin "2") (pinfunction "2_2") (pintype "passive"))
      (node (ref "C80") (pin "2") (pinfunction "2_2") (pintype "passive"))
      (node (ref "C81") (pin "2") (pinfunction "2_2") (pintype "passive"))
      (node (ref "C82") (pin "2") (pinfunction "2_2") (pintype "passive"))
      (node (ref "C83") (pin "2") (pinfunction "2_2") (pintype "passive"))
      (node (ref "C84") (pin "2") (pinfunction "2_2") (pintype "passive"))
      (node (ref "C85") (pin "2") (pinfunction "2_2") (pintype "passive"))
      (node (ref "C86") (pin "2") (pinfunction "2_2") (pintype "passive"))
      (node (ref "C87") (pin "2") (pinfunction "2_2") (pintype "passive"))
      (node (ref "C88") (pin "2") (pinfunction "2_2") (pintype "passive"))
      (node (ref "C89") (pin "2") (pinfunction "2_2") (pintype "passive"))
      (node (ref "C9") (pin "2") (pinfunction "2_2") (pintype "passive"))
      (node (ref "C90") (pin "2") (pinfunction "2_2") (pintype "passive"))
      (node (ref "C91") (pin "1") (pinfunction "1_1") (pintype "passive"))
      (node (ref "C92") (pin "2") (pinfunction "2_2") (pintype "passive"))
      (node (ref "C93") (pin "2") (pinfunction "2_2") (pintype "passive"))
      (node (ref "GND") (pin "TP") (pinfunction "TP_TP") (pintype "input"))
      (node (ref "GND75") (pin "TP") (pinfunction "TP_TP") (pintype "input"))
      (node (ref "GND77") (pin "TP") (pinfunction "TP_TP") (pintype "input"))
      (node (ref "R12") (pin "2") (pinfunction "2_2") (pintype "passive"))
      (node (ref "R15") (pin "2") (pinfunction "2_2") (pintype "passive"))
      (node (ref "R18") (pin "2") (pinfunction "2_2") (pintype "passive"))
      (node (ref "R22") (pin "1") (pinfunction "1_1") (pintype "passive"))
      (node (ref "R2X") (pin "2") (pinfunction "2_2") (pintype "passive"))
      (node (ref "R3") (pin "2") (pinfunction "2_2") (pintype "passive"))
      (node (ref "R6") (pin "2") (pinfunction "2_2") (pintype "passive"))
      (node (ref "R9") (pin "2") (pinfunction "2_2") (pintype "passive"))
      (node (ref "SENSOR") (pin "A21") (pinfunction "GND_A21") (pintype "power_in"))
      (node (ref "SENSOR") (pin "A25") (pinfunction "GND_A25") (pintype "power_in"))
      (node (ref "SENSOR") (pin "A28") (pinfunction "GND_A28") (pintype "power_in"))
      (node (ref "SENSOR") (pin "A29") (pinfunction "GND_A29") (pintype "power_in"))
      (node (ref "SENSOR") (pin "A9") (pinfunction "GND_A9") (pintype "power_in"))
      (node (ref "SENSOR") (pin "B22") (pinfunction "GND_B22") (pintype "power_in"))
      (node (ref "SENSOR") (pin "B26") (pinfunction "GND_B26") (pintype "power_in"))
      (node (ref "SENSOR") (pin "B27") (pinfunction "GND_B27") (pintype "power_in"))
      (node (ref "SENSOR") (pin "B28") (pinfunction "GND_B28") (pintype "power_in"))
      (node (ref "SENSOR") (pin "B5") (pinfunction "GND_B5") (pintype "power_in"))
      (node (ref "SENSOR") (pin "C15") (pinfunction "GND_C15") (pintype "power_in"))
      (node (ref "SENSOR") (pin "C16") (pinfunction "GND_C16") (pintype "power_in"))
      (node (ref "SENSOR") (pin "C28") (pinfunction "GND_C28") (pintype "power_in"))
      (node (ref "SENSOR") (pin "D2") (pinfunction "GND_D2") (pintype "power_in"))
      (node (ref "SENSOR") (pin "D25") (pinfunction "GND_D25") (pintype "power_in"))
      (node (ref "SENSOR") (pin "D27") (pinfunction "GND_D27") (pintype "power_in"))
      (node (ref "SENSOR") (pin "D29") (pinfunction "GND_D29") (pintype "power_in"))
      (node (ref "SENSOR") (pin "E15") (pinfunction "GND_E15") (pintype "power_in"))
      (node (ref "SENSOR") (pin "E16") (pinfunction "GND_E16") (pintype "power_in"))
      (node (ref "SENSOR") (pin "E25") (pinfunction "GND_E25") (pintype "power_in"))
      (node (ref "SENSOR") (pin "E27") (pinfunction "GND_E27") (pintype "power_in"))
      (node (ref "SENSOR") (pin "E3") (pinfunction "GND_E3") (pintype "power_in"))
      (node (ref "SENSOR") (pin "E4") (pinfunction "DIO2_E4") (pintype "output"))
      (node (ref "SENSOR") (pin "F27") (pinfunction "GND_F27") (pintype "power_in"))
      (node (ref "SENSOR") (pin "F4") (pinfunction "DIO1_F4") (pintype "output"))
      (node (ref "SENSOR") (pin "G3") (pinfunction "DIO4_G3") (pintype "output"))
      (node (ref "SENSOR") (pin "G5") (pinfunction "GND_G5") (pintype "power_in"))
      (node (ref "SENSOR") (pin "H1") (pinfunction "GND_H1") (pintype "power_in"))
      (node (ref "SENSOR") (pin "H21") (pinfunction "GND_H21") (pintype "power_in"))
      (node (ref "SENSOR") (pin "H25") (pinfunction "GND_H25") (pintype "power_in"))
      (node (ref "SENSOR") (pin "H27") (pinfunction "GND_H27") (pintype "power_in"))
      (node (ref "SENSOR") (pin "H4") (pinfunction "DIO3_H4") (pintype "output"))
      (node (ref "SENSOR") (pin "H6") (pinfunction "GND_H6") (pintype "power_in"))
      (node (ref "SENSOR") (pin "H9") (pinfunction "GND_H9") (pintype "power_in"))
      (node (ref "U1") (pin "6") (pinfunction "ANODE_6") (pintype "input"))
      (node (ref "U2") (pin "6") (pinfunction "ANODE_6") (pintype "input"))
      (node (ref "U3") (pin "2") (pinfunction "GND_2") (pintype "power_in"))
      (node (ref "U3") (pin "EP") (pinfunction "EP_EP") (pintype "power_in"))
      (node (ref "U4") (pin "16") (pinfunction "DIR2_16") (pintype "input"))
      (node (ref "U4") (pin "7") (pinfunction "~{OE}_7") (pintype "input"))
      (node (ref "U4") (pin "8") (pinfunction "GND_8") (pintype "passive"))
      (node (ref "U5") (pin "6") (pinfunction "DIR4_6") (pintype "input"))
      (node (ref "U5") (pin "7") (pinfunction "~{OE}_7") (pintype "input"))
      (node (ref "U5") (pin "8") (pinfunction "GND_8") (pintype "passive"))
      (node (ref "U6") (pin "16") (pinfunction "DIR2_16") (pintype "input"))
      (node (ref "U6") (pin "7") (pinfunction "~{OE}_7") (pintype "input"))
      (node (ref "U6") (pin "8") (pinfunction "GND_8") (pintype "passive"))
      (node (ref "U7") (pin "4") (pinfunction "GND_4") (pintype "power_in"))
      (node (ref "U7") (pin "5") (pinfunction "A2_5") (pintype "input"))
      (node (ref "U7") (pin "6") (pinfunction "A1_6") (pintype "input"))
      (node (ref "U7") (pin "7") (pinfunction "A0_7") (pintype "input"))
      (node (ref "UEP") (pin "1") (pinfunction "A0_1") (pintype "input"))
      (node (ref "UEP") (pin "2") (pinfunction "A1_2") (pintype "input"))
      (node (ref "UEP") (pin "3") (pinfunction "A2_3") (pintype "input"))
      (node (ref "UEP") (pin "4") (pinfunction "GND_4") (pintype "passive"))
      (node (ref "UEP") (pin "EP") (pinfunction "EP_EP") (pintype "passive"))
      (node (ref "UNE") (pin "4") (pinfunction "VSS_4") (pintype "power_in"))
      (node (ref "UNE") (pin "EP") (pinfunction "EP_EP") (pintype "passive"))
      (node (ref "UNN") (pin "4") (pinfunction "VSS_4") (pintype "power_in"))
      (node (ref "UNN") (pin "EP") (pinfunction "EP_EP") (pintype "passive"))
      (node (ref "UNW") (pin "4") (pinfunction "VSS_4") (pintype "power_in"))
      (node (ref "UNW") (pin "EP") (pinfunction "EP_EP") (pintype "passive"))
      (node (ref "USE") (pin "4") (pinfunction "VSS_4") (pintype "power_in"))
      (node (ref "USE") (pin "EP") (pinfunction "EP_EP") (pintype "passive"))
      (node (ref "USS") (pin "4") (pinfunction "VSS_4") (pintype "power_in"))
      (node (ref "USS") (pin "EP") (pinfunction "EP_EP") (pintype "passive"))
      (node (ref "USW") (pin "4") (pinfunction "VSS_4") (pintype "power_in"))
      (node (ref "USW") (pin "EP") (pinfunction "EP_EP") (pintype "passive"))
      (node (ref "X-NORTH") (pin "102") (pinfunction "102_102") (pintype "bidirectional"))
      (node (ref "X-NORTH") (pin "103") (pinfunction "103_103") (pintype "bidirectional"))
      (node (ref "X-NORTH") (pin "108") (pinfunction "108_108") (pintype "bidirectional"))
      (node (ref "X-NORTH") (pin "114") (pinfunction "114_114") (pintype "bidirectional"))
      (node (ref "X-NORTH") (pin "12") (pinfunction "12_12") (pintype "bidirectional"))
      (node (ref "X-NORTH") (pin "120") (pinfunction "120_120") (pintype "bidirectional"))
      (node (ref "X-NORTH") (pin "126") (pinfunction "126_126") (pintype "bidirectional"))
      (node (ref "X-NORTH") (pin "132") (pinfunction "132_132") (pintype "bidirectional"))
      (node (ref "X-NORTH") (pin "138") (pinfunction "138_138") (pintype "bidirectional"))
      (node (ref "X-NORTH") (pin "139") (pinfunction "139_139") (pintype "bidirectional"))
      (node (ref "X-NORTH") (pin "18") (pinfunction "18_18") (pintype "bidirectional"))
      (node (ref "X-NORTH") (pin "24") (pinfunction "24_24") (pintype "bidirectional"))
      (node (ref "X-NORTH") (pin "30") (pinfunction "30_30") (pintype "bidirectional"))
      (node (ref "X-NORTH") (pin "36") (pinfunction "36_36") (pintype "bidirectional"))
      (node (ref "X-NORTH") (pin "42") (pinfunction "42_42") (pintype "bidirectional"))
      (node (ref "X-NORTH") (pin "43") (pinfunction "43_43") (pintype "bidirectional"))
      (node (ref "X-NORTH") (pin "48") (pinfunction "48_48") (pintype "bidirectional"))
      (node (ref "X-NORTH") (pin "54") (pinfunction "54_54") (pintype "bidirectional"))
      (node (ref "X-NORTH") (pin "60") (pinfunction "60_60") (pintype "bidirectional"))
      (node (ref "X-NORTH") (pin "66") (pinfunction "66_66") (pintype "bidirectional"))
      (node (ref "X-NORTH") (pin "72") (pinfunction "72_72") (pintype "bidirectional"))
      (node (ref "X-NORTH") (pin "78") (pinfunction "78_78") (pintype "bidirectional"))
      (node (ref "X-NORTH") (pin "84") (pinfunction "84_84") (pintype "bidirectional"))
      (node (ref "X-NORTH") (pin "90") (pinfunction "90_90") (pintype "bidirectional"))
      (node (ref "X-NORTH") (pin "96") (pinfunction "96_96") (pintype "bidirectional"))
      (node (ref "X-SOUTH") (pin "102") (pinfunction "102_102") (pintype "bidirectional"))
      (node (ref "X-SOUTH") (pin "103") (pinfunction "103_103") (pintype "bidirectional"))
      (node (ref "X-SOUTH") (pin "108") (pinfunction "108_108") (pintype "bidirectional"))
      (node (ref "X-SOUTH") (pin "114") (pinfunction "114_114") (pintype "bidirectional"))
      (node (ref "X-SOUTH") (pin "12") (pinfunction "12_12") (pintype "bidirectional"))
      (node (ref "X-SOUTH") (pin "120") (pinfunction "120_120") (pintype "bidirectional"))
      (node (ref "X-SOUTH") (pin "126") (pinfunction "126_126") (pintype "bidirectional"))
      (node (ref "X-SOUTH") (pin "132") (pinfunction "132_132") (pintype "bidirectional"))
      (node (ref "X-SOUTH") (pin "138") (pinfunction "138_138") (pintype "bidirectional"))
      (node (ref "X-SOUTH") (pin "139") (pinfunction "139_139") (pintype "bidirectional"))
      (node (ref "X-SOUTH") (pin "18") (pinfunction "18_18") (pintype "bidirectional"))
      (node (ref "X-SOUTH") (pin "24") (pinfunction "24_24") (pintype "bidirectional"))
      (node (ref "X-SOUTH") (pin "30") (pinfunction "30_30") (pintype "bidirectional"))
      (node (ref "X-SOUTH") (pin "36") (pinfunction "36_36") (pintype "bidirectional"))
      (node (ref "X-SOUTH") (pin "42") (pinfunction "42_42") (pintype "bidirectional"))
      (node (ref "X-SOUTH") (pin "43") (pinfunction "43_43") (pintype "bidirectional"))
      (node (ref "X-SOUTH") (pin "48") (pinfunction "48_48") (pintype "bidirectional"))
      (node (ref "X-SOUTH") (pin "54") (pinfunction "54_54") (pintype "bidirectional"))
      (node (ref "X-SOUTH") (pin "60") (pinfunction "60_60") (pintype "bidirectional"))
      (node (ref "X-SOUTH") (pin "66") (pinfunction "66_66") (pintype "bidirectional"))
      (node (ref "X-SOUTH") (pin "72") (pinfunction "72_72") (pintype "bidirectional"))
      (node (ref "X-SOUTH") (pin "78") (pinfunction "78_78") (pintype "bidirectional"))
      (node (ref "X-SOUTH") (pin "84") (pinfunction "84_84") (pintype "bidirectional"))
      (node (ref "X-SOUTH") (pin "90") (pinfunction "90_90") (pintype "bidirectional"))
      (node (ref "X-SOUTH") (pin "96") (pinfunction "96_96") (pintype "bidirectional"))
    )
    (net (code "4") (name "N$42") (class "Default")
      (node (ref "SENSOR") (pin "A2") (pinfunction "TANA_A2") (pintype "output"))
    )
    (net (code "5") (name "N00_N") (class "Default")
      (node (ref "R25") (pin "2") (pinfunction "2_2") (pintype "passive"))
      (node (ref "SENSOR") (pin "E6") (pinfunction "LVDS_CLK_P_E6") (pintype "input"))
      (node (ref "X-NORTH") (pin "16") (pinfunction "16_16") (pintype "bidirectional"))
    )
    (net (code "6") (name "N00_P") (class "Default")
      (node (ref "R25") (pin "1") (pinfunction "1_1") (pintype "passive"))
      (node (ref "SENSOR") (pin "E5") (pinfunction "LVDS_CLK_N_E5") (pintype "input"))
      (node (ref "X-NORTH") (pin "14") (pinfunction "14_14") (pintype "bidirectional"))
    )
    (net (code "7") (name "N01_N") (class "Default")
      (node (ref "SENSOR") (pin "G7") (pinfunction "OUTCLK_P_G7") (pintype "output"))
      (node (ref "X-NORTH") (pin "17") (pinfunction "17_17") (pintype "bidirectional"))
    )
    (net (code "8") (name "N01_P") (class "Default")
      (node (ref "SENSOR") (pin "G6") (pinfunction "OUTCLK_N_G6") (pintype "output"))
      (node (ref "X-NORTH") (pin "15") (pinfunction "15_15") (pintype "bidirectional"))
    )
    (net (code "9") (name "N02_N") (class "Default")
      (node (ref "SENSOR") (pin "F7") (pinfunction "OUT33_P_F7") (pintype "output"))
      (node (ref "X-NORTH") (pin "22") (pinfunction "22_22") (pintype "bidirectional"))
    )
    (net (code "10") (name "N02_P") (class "Default")
      (node (ref "SENSOR") (pin "F6") (pinfunction "OUT33_N_F6") (pintype "output"))
      (node (ref "X-NORTH") (pin "20") (pinfunction "20_20") (pintype "bidirectional"))
    )
    (net (code "11") (name "N03_N") (class "Default")
      (node (ref "X-NORTH") (pin "23") (pinfunction "23_23") (pintype "bidirectional"))
    )
    (net (code "12") (name "N03_P") (class "Default")
      (node (ref "X-NORTH") (pin "21") (pinfunction "21_21") (pintype "bidirectional"))
    )
    (net (code "13") (name "N04_N") (class "Default")
      (node (ref "SENSOR") (pin "E8") (pinfunction "OUT35_P_E8") (pintype "output"))
      (node (ref "X-NORTH") (pin "28") (pinfunction "28_28") (pintype "bidirectional"))
    )
    (net (code "14") (name "N04_P") (class "Default")
      (node (ref "SENSOR") (pin "E7") (pinfunction "OUT35_N_E7") (pintype "output"))
      (node (ref "X-NORTH") (pin "26") (pinfunction "26_26") (pintype "bidirectional"))
    )
    (net (code "15") (name "N05_N") (class "Default")
      (node (ref "SENSOR") (pin "H8") (pinfunction "OUT34_P_H8") (pintype "output"))
      (node (ref "X-NORTH") (pin "29") (pinfunction "29_29") (pintype "bidirectional"))
    )
    (net (code "16") (name "N05_P") (class "Default")
      (node (ref "SENSOR") (pin "H7") (pinfunction "OUT34_N_H7") (pintype "output"))
      (node (ref "X-NORTH") (pin "27") (pinfunction "27_27") (pintype "bidirectional"))
    )
    (net (code "17") (name "N06_N") (class "Default")
      (node (ref "SENSOR") (pin "F9") (pinfunction "OUT37_P_F9") (pintype "output"))
      (node (ref "X-NORTH") (pin "34") (pinfunction "34_34") (pintype "bidirectional"))
    )
    (net (code "18") (name "N06_P") (class "Default")
      (node (ref "SENSOR") (pin "F8") (pinfunction "OUT37_N_F8") (pintype "output"))
      (node (ref "X-NORTH") (pin "32") (pinfunction "32_32") (pintype "bidirectional"))
    )
    (net (code "19") (name "N07_N") (class "Default")
      (node (ref "SENSOR") (pin "G9") (pinfunction "OUT36_P_G9") (pintype "output"))
      (node (ref "X-NORTH") (pin "35") (pinfunction "35_35") (pintype "bidirectional"))
    )
    (net (code "20") (name "N07_P") (class "Default")
      (node (ref "SENSOR") (pin "G8") (pinfunction "OUT36_N_G8") (pintype "output"))
      (node (ref "X-NORTH") (pin "33") (pinfunction "33_33") (pintype "bidirectional"))
    )
    (net (code "21") (name "N08_N") (class "Default")
      (node (ref "SENSOR") (pin "E10") (pinfunction "OUT38_P_E10") (pintype "output"))
      (node (ref "X-NORTH") (pin "40") (pinfunction "40_40") (pintype "bidirectional"))
    )
    (net (code "22") (name "N08_P") (class "Default")
      (node (ref "SENSOR") (pin "E9") (pinfunction "OUT38_N_E9") (pintype "output"))
      (node (ref "X-NORTH") (pin "38") (pinfunction "38_38") (pintype "bidirectional"))
    )
    (net (code "23") (name "N09_N") (class "Default")
      (node (ref "SENSOR") (pin "G11") (pinfunction "OUT39_P_G11") (pintype "output"))
      (node (ref "X-NORTH") (pin "41") (pinfunction "41_41") (pintype "bidirectional"))
    )
    (net (code "24") (name "N09_P") (class "Default")
      (node (ref "SENSOR") (pin "G10") (pinfunction "OUT39_N_G10") (pintype "output"))
      (node (ref "X-NORTH") (pin "39") (pinfunction "39_39") (pintype "bidirectional"))
    )
    (net (code "25") (name "N10_N") (class "Default")
      (node (ref "SENSOR") (pin "F11") (pinfunction "OUT40_P_F11") (pintype "output"))
      (node (ref "X-NORTH") (pin "46") (pinfunction "46_46") (pintype "bidirectional"))
    )
    (net (code "26") (name "N10_P") (class "Default")
      (node (ref "SENSOR") (pin "F10") (pinfunction "OUT40_N_F10") (pintype "output"))
      (node (ref "X-NORTH") (pin "44") (pinfunction "44_44") (pintype "bidirectional"))
    )
    (net (code "27") (name "N11_N") (class "Default")
      (node (ref "SENSOR") (pin "H12") (pinfunction "OUT41_P_H12") (pintype "output"))
      (node (ref "X-NORTH") (pin "47") (pinfunction "47_47") (pintype "bidirectional"))
    )
    (net (code "28") (name "N11_P") (class "Default")
      (node (ref "SENSOR") (pin "H11") (pinfunction "OUT41_N_H11") (pintype "output"))
      (node (ref "X-NORTH") (pin "45") (pinfunction "45_45") (pintype "bidirectional"))
    )
    (net (code "29") (name "N12_N") (class "Default")
      (node (ref "SENSOR") (pin "E12") (pinfunction "OUT42_P_E12") (pintype "output"))
      (node (ref "X-NORTH") (pin "52") (pinfunction "52_52") (pintype "bidirectional"))
    )
    (net (code "30") (name "N12_P") (class "Default")
      (node (ref "SENSOR") (pin "E11") (pinfunction "OUT42_N_E11") (pintype "output"))
      (node (ref "X-NORTH") (pin "50") (pinfunction "50_50") (pintype "bidirectional"))
    )
    (net (code "31") (name "N13_N") (class "Default")
      (node (ref "SENSOR") (pin "G13") (pinfunction "OUT43_P_G13") (pintype "output"))
      (node (ref "X-NORTH") (pin "53") (pinfunction "53_53") (pintype "bidirectional"))
    )
    (net (code "32") (name "N13_P") (class "Default")
      (node (ref "SENSOR") (pin "G12") (pinfunction "OUT43_N_G12") (pintype "output"))
      (node (ref "X-NORTH") (pin "51") (pinfunction "51_51") (pintype "bidirectional"))
    )
    (net (code "33") (name "N14_N") (class "Default")
      (node (ref "SENSOR") (pin "F13") (pinfunction "OUT44_P_F13") (pintype "output"))
      (node (ref "X-NORTH") (pin "58") (pinfunction "58_58") (pintype "bidirectional"))
    )
    (net (code "34") (name "N14_P") (class "Default")
      (node (ref "SENSOR") (pin "F12") (pinfunction "OUT44_N_F12") (pintype "output"))
      (node (ref "X-NORTH") (pin "56") (pinfunction "56_56") (pintype "bidirectional"))
    )
    (net (code "35") (name "N15_N") (class "Default")
      (node (ref "SENSOR") (pin "H14") (pinfunction "OUT45_P_H14") (pintype "output"))
      (node (ref "X-NORTH") (pin "59") (pinfunction "59_59") (pintype "bidirectional"))
    )
    (net (code "36") (name "N15_P") (class "Default")
      (node (ref "SENSOR") (pin "H13") (pinfunction "OUT45_N_H13") (pintype "output"))
      (node (ref "X-NORTH") (pin "57") (pinfunction "57_57") (pintype "bidirectional"))
    )
    (net (code "37") (name "N16_N") (class "Default")
      (node (ref "SENSOR") (pin "E14") (pinfunction "OUT46_P_E14") (pintype "output"))
      (node (ref "X-NORTH") (pin "64") (pinfunction "64_64") (pintype "bidirectional"))
    )
    (net (code "38") (name "N16_P") (class "Default")
      (node (ref "SENSOR") (pin "E13") (pinfunction "OUT46_N_E13") (pintype "output"))
      (node (ref "X-NORTH") (pin "62") (pinfunction "62_62") (pintype "bidirectional"))
    )
    (net (code "39") (name "N17_N") (class "Default")
      (node (ref "SENSOR") (pin "G15") (pinfunction "OUT47_P_G15") (pintype "output"))
      (node (ref "X-NORTH") (pin "65") (pinfunction "65_65") (pintype "bidirectional"))
    )
    (net (code "40") (name "N17_P") (class "Default")
      (node (ref "SENSOR") (pin "G14") (pinfunction "OUT47_N_G14") (pintype "output"))
      (node (ref "X-NORTH") (pin "63") (pinfunction "63_63") (pintype "bidirectional"))
    )
    (net (code "41") (name "N18_N") (class "Default")
      (node (ref "SENSOR") (pin "F15") (pinfunction "OUT48_P_F15") (pintype "output"))
      (node (ref "X-NORTH") (pin "70") (pinfunction "70_70") (pintype "bidirectional"))
    )
    (net (code "42") (name "N18_P") (class "Default")
      (node (ref "SENSOR") (pin "F14") (pinfunction "OUT48_N_F14") (pintype "output"))
      (node (ref "X-NORTH") (pin "68") (pinfunction "68_68") (pintype "bidirectional"))
    )
    (net (code "43") (name "N19_N") (class "Default")
      (node (ref "SENSOR") (pin "G17") (pinfunction "OUT50_P_G17") (pintype "output"))
      (node (ref "X-NORTH") (pin "71") (pinfunction "71_71") (pintype "bidirectional"))
    )
    (net (code "44") (name "N19_P") (class "Default")
      (node (ref "SENSOR") (pin "G16") (pinfunction "OUT50_N_G16") (pintype "output"))
      (node (ref "X-NORTH") (pin "69") (pinfunction "69_69") (pintype "bidirectional"))
    )
    (net (code "45") (name "N20_N") (class "Default")
      (node (ref "SENSOR") (pin "F17") (pinfunction "OUT49_P_F17") (pintype "output"))
      (node (ref "X-NORTH") (pin "76") (pinfunction "76_76") (pintype "bidirectional"))
    )
    (net (code "46") (name "N20_P") (class "Default")
      (node (ref "SENSOR") (pin "F16") (pinfunction "OUT49_N_F16") (pintype "output"))
      (node (ref "X-NORTH") (pin "74") (pinfunction "74_74") (pintype "bidirectional"))
    )
    (net (code "47") (name "N21_N") (class "Default")
      (node (ref "SENSOR") (pin "H18") (pinfunction "OUT52_P_H18") (pintype "output"))
      (node (ref "X-NORTH") (pin "77") (pinfunction "77_77") (pintype "bidirectional"))
    )
    (net (code "48") (name "N21_P") (class "Default")
      (node (ref "SENSOR") (pin "H17") (pinfunction "OUT52_N_H17") (pintype "output"))
      (node (ref "X-NORTH") (pin "75") (pinfunction "75_75") (pintype "bidirectional"))
    )
    (net (code "49") (name "N22_N") (class "Default")
      (node (ref "SENSOR") (pin "E18") (pinfunction "OUT51_P_E18") (pintype "output"))
      (node (ref "X-NORTH") (pin "82") (pinfunction "82_82") (pintype "bidirectional"))
    )
    (net (code "50") (name "N22_P") (class "Default")
      (node (ref "SENSOR") (pin "E17") (pinfunction "OUT51_N_E17") (pintype "output"))
      (node (ref "X-NORTH") (pin "80") (pinfunction "80_80") (pintype "bidirectional"))
    )
    (net (code "51") (name "N23_N") (class "Default")
      (node (ref "SENSOR") (pin "G19") (pinfunction "OUT54_P_G19") (pintype "output"))
      (node (ref "X-NORTH") (pin "83") (pinfunction "83_83") (pintype "bidirectional"))
    )
    (net (code "52") (name "N23_P") (class "Default")
      (node (ref "SENSOR") (pin "G18") (pinfunction "OUT54_N_G18") (pintype "output"))
      (node (ref "X-NORTH") (pin "81") (pinfunction "81_81") (pintype "bidirectional"))
    )
    (net (code "53") (name "N24_N") (class "Default")
      (node (ref "SENSOR") (pin "F19") (pinfunction "OUT53_P_F19") (pintype "output"))
      (node (ref "X-NORTH") (pin "88") (pinfunction "88_88") (pintype "bidirectional"))
    )
    (net (code "54") (name "N24_P") (class "Default")
      (node (ref "SENSOR") (pin "F18") (pinfunction "OUT53_N_F18") (pintype "output"))
      (node (ref "X-NORTH") (pin "86") (pinfunction "86_86") (pintype "bidirectional"))
    )
    (net (code "55") (name "N25_N") (class "Default")
      (node (ref "SENSOR") (pin "H20") (pinfunction "OUT56_P_H20") (pintype "output"))
      (node (ref "X-NORTH") (pin "89") (pinfunction "89_89") (pintype "bidirectional"))
    )
    (net (code "56") (name "N25_P") (class "Default")
      (node (ref "SENSOR") (pin "H19") (pinfunction "OUT56_N_H19") (pintype "output"))
      (node (ref "X-NORTH") (pin "87") (pinfunction "87_87") (pintype "bidirectional"))
    )
    (net (code "57") (name "N26_N") (class "Default")
      (node (ref "SENSOR") (pin "E20") (pinfunction "OUT55_P_E20") (pintype "output"))
      (node (ref "X-NORTH") (pin "94") (pinfunction "94_94") (pintype "bidirectional"))
    )
    (net (code "58") (name "N26_P") (class "Default")
      (node (ref "SENSOR") (pin "E19") (pinfunction "OUT55_N_E19") (pintype "output"))
      (node (ref "X-NORTH") (pin "92") (pinfunction "92_92") (pintype "bidirectional"))
    )
    (net (code "59") (name "N27_N") (class "Default")
      (node (ref "SENSOR") (pin "G21") (pinfunction "OUT58_P_G21") (pintype "output"))
      (node (ref "X-NORTH") (pin "95") (pinfunction "95_95") (pintype "bidirectional"))
    )
    (net (code "60") (name "N27_P") (class "Default")
      (node (ref "SENSOR") (pin "G20") (pinfunction "OUT58_N_G20") (pintype "output"))
      (node (ref "X-NORTH") (pin "93") (pinfunction "93_93") (pintype "bidirectional"))
    )
    (net (code "61") (name "N28_N") (class "Default")
      (node (ref "SENSOR") (pin "F21") (pinfunction "OUT57_P_F21") (pintype "output"))
      (node (ref "X-NORTH") (pin "100") (pinfunction "100_100") (pintype "bidirectional"))
    )
    (net (code "62") (name "N28_P") (class "Default")
      (node (ref "SENSOR") (pin "F20") (pinfunction "OUT57_N_F20") (pintype "output"))
      (node (ref "X-NORTH") (pin "98") (pinfunction "98_98") (pintype "bidirectional"))
    )
    (net (code "63") (name "N29_N") (class "Default")
      (node (ref "SENSOR") (pin "G23") (pinfunction "OUT61_P_G23") (pintype "output"))
      (node (ref "X-NORTH") (pin "101") (pinfunction "101_101") (pintype "bidirectional"))
    )
    (net (code "64") (name "N29_P") (class "Default")
      (node (ref "SENSOR") (pin "G22") (pinfunction "OUT61_N_G22") (pintype "output"))
      (node (ref "X-NORTH") (pin "99") (pinfunction "99_99") (pintype "bidirectional"))
    )
    (net (code "65") (name "N30_N") (class "Default")
      (node (ref "SENSOR") (pin "E22") (pinfunction "OUT59_P_E22") (pintype "output"))
      (node (ref "X-NORTH") (pin "106") (pinfunction "106_106") (pintype "bidirectional"))
    )
    (net (code "66") (name "N30_P") (class "Default")
      (node (ref "SENSOR") (pin "E21") (pinfunction "OUT59_N_E21") (pintype "output"))
      (node (ref "X-NORTH") (pin "104") (pinfunction "104_104") (pintype "bidirectional"))
    )
    (net (code "67") (name "N31_N") (class "Default")
      (node (ref "SENSOR") (pin "H24") (pinfunction "OUT63_P_H24") (pintype "output"))
      (node (ref "X-NORTH") (pin "107") (pinfunction "107_107") (pintype "bidirectional"))
    )
    (net (code "68") (name "N31_P") (class "Default")
      (node (ref "SENSOR") (pin "H23") (pinfunction "OUT63_N_H23") (pintype "output"))
      (node (ref "X-NORTH") (pin "105") (pinfunction "105_105") (pintype "bidirectional"))
    )
    (net (code "69") (name "N32_N") (class "Default")
      (node (ref "SENSOR") (pin "F23") (pinfunction "OUT60_P_F23") (pintype "output"))
      (node (ref "X-NORTH") (pin "112") (pinfunction "112_112") (pintype "bidirectional"))
    )
    (net (code "70") (name "N32_P") (class "Default")
      (node (ref "SENSOR") (pin "F22") (pinfunction "OUT60_N_F22") (pintype "output"))
      (node (ref "X-NORTH") (pin "110") (pinfunction "110_110") (pintype "bidirectional"))
    )
    (net (code "71") (name "N33_N") (class "Default")
      (node (ref "SENSOR") (pin "G25") (pinfunction "OUT64_P_G25") (pintype "output"))
      (node (ref "X-NORTH") (pin "113") (pinfunction "113_113") (pintype "bidirectional"))
    )
    (net (code "72") (name "N33_P") (class "Default")
      (node (ref "SENSOR") (pin "G24") (pinfunction "OUT64_N_G24") (pintype "output"))
      (node (ref "X-NORTH") (pin "111") (pinfunction "111_111") (pintype "bidirectional"))
    )
    (net (code "73") (name "N34_N") (class "Default")
      (node (ref "SENSOR") (pin "E24") (pinfunction "OUT62_P_E24") (pintype "output"))
      (node (ref "X-NORTH") (pin "118") (pinfunction "118_118") (pintype "bidirectional"))
    )
    (net (code "74") (name "N34_P") (class "Default")
      (node (ref "SENSOR") (pin "E23") (pinfunction "OUT62_N_E23") (pintype "output"))
      (node (ref "X-NORTH") (pin "116") (pinfunction "116_116") (pintype "bidirectional"))
    )
    (net (code "75") (name "N35_N") (class "Default")
      (node (ref "U6") (pin "4") (pinfunction "A4_4") (pintype "bidirectional"))
      (node (ref "X-NORTH") (pin "119") (pinfunction "119_119") (pintype "bidirectional"))
    )
    (net (code "76") (name "N35_P") (class "Default")
      (node (ref "U6") (pin "3") (pinfunction "A3_3") (pintype "bidirectional"))
      (node (ref "X-NORTH") (pin "117") (pinfunction "117_117") (pintype "bidirectional"))
    )
    (net (code "77") (name "N36_N") (class "Default")
      (node (ref "X-NORTH") (pin "124") (pinfunction "124_124") (pintype "bidirectional"))
    )
    (net (code "78") (name "N36_P") (class "Default")
      (node (ref "X-NORTH") (pin "122") (pinfunction "122_122") (pintype "bidirectional"))
    )
    (net (code "79") (name "N37_N") (class "Default")
      (node (ref "U5") (pin "3") (pinfunction "A3_3") (pintype "bidirectional"))
      (node (ref "X-NORTH") (pin "125") (pinfunction "125_125") (pintype "bidirectional"))
    )
    (net (code "80") (name "N37_P") (class "Default")
      (node (ref "U5") (pin "4") (pinfunction "A4_4") (pintype "bidirectional"))
      (node (ref "X-NORTH") (pin "123") (pinfunction "123_123") (pintype "bidirectional"))
    )
    (net (code "81") (name "N38_N") (class "Default")
      (node (ref "U6") (pin "2") (pinfunction "A2_2") (pintype "bidirectional"))
      (node (ref "X-NORTH") (pin "130") (pinfunction "130_130") (pintype "bidirectional"))
    )
    (net (code "82") (name "N38_P") (class "Default")
      (node (ref "U6") (pin "1") (pinfunction "A1_1") (pintype "bidirectional"))
      (node (ref "X-NORTH") (pin "128") (pinfunction "128_128") (pintype "bidirectional"))
    )
    (net (code "83") (name "N39_N") (class "Default")
      (node (ref "U5") (pin "1") (pinfunction "A1_1") (pintype "bidirectional"))
      (node (ref "X-NORTH") (pin "131") (pinfunction "131_131") (pintype "bidirectional"))
    )
    (net (code "84") (name "N39_P") (class "Default")
      (node (ref "U5") (pin "2") (pinfunction "A2_2") (pintype "bidirectional"))
      (node (ref "X-NORTH") (pin "129") (pinfunction "129_129") (pintype "bidirectional"))
    )
    (net (code "85") (name "N_CHK_EN") (class "Default")
      (node (ref "X-NORTH") (pin "8") (pinfunction "8_8") (pintype "bidirectional"))
    )
    (net (code "86") (name "N_CHK_V") (class "Default")
      (node (ref "C2") (pin "1") (pinfunction "1_1") (pintype "passive"))
      (node (ref "C3") (pin "1") (pinfunction "1_1") (pintype "passive"))
      (node (ref "C4") (pin "1") (pinfunction "1_1") (pintype "passive"))
      (node (ref "R19") (pin "1") (pinfunction "1_1") (pintype "passive"))
      (node (ref "TP1") (pin "TP") (pinfunction "TP_TP") (pintype "input"))
      (node (ref "UNE") (pin "8") (pinfunction "VDD_8") (pintype "power_in"))
      (node (ref "UNN") (pin "8") (pinfunction "VDD_8") (pintype "power_in"))
      (node (ref "UNW") (pin "8") (pinfunction "VDD_8") (pintype "power_in"))
      (node (ref "X-NORTH") (pin "10") (pinfunction "10_10") (pintype "bidirectional"))
    )
    (net (code "87") (name "N_I2C_EN") (class "Default")
      (node (ref "X-NORTH") (pin "137") (pinfunction "137_137") (pintype "bidirectional"))
    )
    (net (code "88") (name "N_I2C_V") (class "Default")
      (node (ref "C1") (pin "1") (pinfunction "1_1") (pintype "passive"))
      (node (ref "R1X") (pin "1") (pinfunction "1_1") (pintype "passive"))
      (node (ref "UEP") (pin "8") (pinfunction "VCC_8") (pintype "power_in"))
      (node (ref "X-NORTH") (pin "135") (pinfunction "135_135") (pintype "bidirectional"))
    )
    (net (code "89") (name "N_REF") (class "Default")
      (node (ref "R19") (pin "2") (pinfunction "2_2") (pintype "passive"))
      (node (ref "TP2") (pin "TP") (pinfunction "TP_TP") (pintype "input"))
      (node (ref "U1") (pin "1") (pinfunction "CATHODE_1") (pintype "output"))
      (node (ref "U1") (pin "3") (pinfunction "REF_3") (pintype "input"))
      (node (ref "UNE") (pin "2") (pinfunction "VINA-_2") (pintype "input"))
      (node (ref "UNE") (pin "5") (pinfunction "VINB+_5") (pintype "input"))
      (node (ref "UNN") (pin "2") (pinfunction "VINA-_2") (pintype "input"))
      (node (ref "UNN") (pin "5") (pinfunction "VINB+_5") (pintype "input"))
      (node (ref "UNW") (pin "2") (pinfunction "VINA-_2") (pintype "input"))
      (node (ref "UNW") (pin "5") (pinfunction "VINB+_5") (pintype "input"))
    )
    (net (code "90") (name "N_SCK") (class "Default")
      (node (ref "U4") (pin "4") (pinfunction "A4_4") (pintype "bidirectional"))
      (node (ref "X-NORTH") (pin "144") (pinfunction "144_144") (pintype "bidirectional"))
    )
    (net (code "91") (name "N_SCL") (class "Default")
      (node (ref "UEP") (pin "6") (pinfunction "SCL_6") (pintype "input"))
      (node (ref "X-NORTH") (pin "143") (pinfunction "143_143") (pintype "bidirectional"))
    )
    (net (code "92") (name "N_SDA") (class "Default")
      (node (ref "UEP") (pin "5") (pinfunction "SDA_5") (pintype "bidirectional"))
      (node (ref "X-NORTH") (pin "141") (pinfunction "141_141") (pintype "bidirectional"))
    )
    (net (code "93") (name "N_SDI") (class "Default")
      (node (ref "U4") (pin "2") (pinfunction "A2_2") (pintype "bidirectional"))
      (node (ref "X-NORTH") (pin "140") (pinfunction "140_140") (pintype "bidirectional"))
    )
    (net (code "94") (name "N_SDO") (class "Default")
      (node (ref "U4") (pin "3") (pinfunction "A3_3") (pintype "bidirectional"))
      (node (ref "X-NORTH") (pin "142") (pinfunction "142_142") (pintype "bidirectional"))
    )
    (net (code "95") (name "N_SPI_EN") (class "Default")
      (node (ref "U4") (pin "1") (pinfunction "A1_1") (pintype "bidirectional"))
      (node (ref "X-NORTH") (pin "136") (pinfunction "136_136") (pintype "bidirectional"))
    )
    (net (code "96") (name "N_SPI_V") (class "Default")
      (node (ref "C59") (pin "1") (pinfunction "1_1") (pintype "passive"))
      (node (ref "U4") (pin "14") (pinfunction "VCCA_14") (pintype "power_in"))
      (node (ref "U4") (pin "15") (pinfunction "DIR1_15") (pintype "input"))
      (node (ref "U4") (pin "5") (pinfunction "DIR3_5") (pintype "input"))
      (node (ref "U4") (pin "6") (pinfunction "DIR4_6") (pintype "input"))
      (node (ref "X-NORTH") (pin "134") (pinfunction "134_134") (pintype "bidirectional"))
    )
    (net (code "97") (name "N_VE") (class "Default")
      (node (ref "C22") (pin "1") (pinfunction "1_1") (pintype "passive"))
      (node (ref "C23") (pin "1") (pinfunction "1_1") (pintype "passive"))
      (node (ref "C24") (pin "1") (pinfunction "1_1") (pintype "passive"))
      (node (ref "C25") (pin "1") (pinfunction "1_1") (pintype "passive"))
      (node (ref "C26") (pin "1") (pinfunction "1_1") (pintype "passive"))
      (node (ref "C27") (pin "1") (pinfunction "1_1") (pintype "passive"))
      (node (ref "C28") (pin "1") (pinfunction "1_1") (pintype "passive"))
      (node (ref "C50") (pin "1") (pinfunction "1_1") (pintype "passive"))
      (node (ref "C51") (pin "1") (pinfunction "1_1") (pintype "passive"))
      (node (ref "C52") (pin "1") (pinfunction "1_1") (pintype "passive"))
      (node (ref "C53") (pin "1") (pinfunction "1_1") (pintype "passive"))
      (node (ref "C54") (pin "1") (pinfunction "1_1") (pintype "passive"))
      (node (ref "C55") (pin "1") (pinfunction "1_1") (pintype "passive"))
      (node (ref "C56") (pin "1") (pinfunction "1_1") (pintype "passive"))
      (node (ref "C67") (pin "1") (pinfunction "1_1") (pintype "passive"))
      (node (ref "C69") (pin "1") (pinfunction "1_1") (pintype "passive"))
      (node (ref "C75") (pin "1") (pinfunction "1_1") (pintype "passive"))
      (node (ref "C76") (pin "1") (pinfunction "1_1") (pintype "passive"))
      (node (ref "C77") (pin "1") (pinfunction "1_1") (pintype "passive"))
      (node (ref "C84") (pin "1") (pinfunction "1_1") (pintype "passive"))
      (node (ref "C85") (pin "1") (pinfunction "1_1") (pintype "passive"))
      (node (ref "C86") (pin "1") (pinfunction "1_1") (pintype "passive"))
      (node (ref "C93") (pin "1") (pinfunction "1_1") (pintype "passive"))
      (node (ref "SENSOR") (pin "C26") (pinfunction "VDD33_C26") (pintype "power_in"))
      (node (ref "SENSOR") (pin "C27") (pinfunction "VDD33_C27") (pintype "power_in"))
      (node (ref "SENSOR") (pin "D26") (pinfunction "VDD33_D26") (pintype "power_in"))
      (node (ref "SENSOR") (pin "D3") (pinfunction "VDD33_D3") (pintype "power_in"))
      (node (ref "SENSOR") (pin "E26") (pinfunction "VDD33_E26") (pintype "power_in"))
      (node (ref "SENSOR") (pin "F26") (pinfunction "VDD33_F26") (pintype "power_in"))
      (node (ref "SENSOR") (pin "F5") (pinfunction "VDD33_F5") (pintype "power_in"))
      (node (ref "TP7") (pin "TP") (pinfunction "TP_TP") (pintype "input"))
      (node (ref "U4") (pin "13") (pinfunction "VCCB_13") (pintype "power_in"))
      (node (ref "U5") (pin "13") (pinfunction "VCCB_13") (pintype "power_in"))
      (node (ref "U6") (pin "13") (pinfunction "VCCB_13") (pintype "power_in"))
      (node (ref "X-NORTH") (pin "109") (pinfunction "109_109") (pintype "bidirectional"))
      (node (ref "X-NORTH") (pin "115") (pinfunction "115_115") (pintype "bidirectional"))
      (node (ref "X-NORTH") (pin "121") (pinfunction "121_121") (pintype "bidirectional"))
      (node (ref "X-NORTH") (pin "127") (pinfunction "127_127") (pintype "bidirectional"))
      (node (ref "X-NORTH") (pin "133") (pinfunction "133_133") (pintype "bidirectional"))
    )
    (net (code "98") (name "N_VE_CV") (class "Default")
      (node (ref "C10") (pin "1") (pinfunction "1_1") (pintype "passive"))
      (node (ref "R7") (pin "1") (pinfunction "1_1") (pintype "passive"))
      (node (ref "X-NORTH") (pin "6") (pinfunction "6_6") (pintype "bidirectional"))
    )
    (net (code "99") (name "N_VE_OV") (class "Default")
      (node (ref "UNE") (pin "7") (pinfunction "OUTB_7") (pintype "output"))
      (node (ref "X-NORTH") (pin "5") (pinfunction "5_5") (pintype "bidirectional"))
    )
    (net (code "100") (name "N_VE_UV") (class "Default")
      (node (ref "UNE") (pin "1") (pinfunction "OUTA_1") (pintype "output"))
      (node (ref "X-NORTH") (pin "11") (pinfunction "11_11") (pintype "bidirectional"))
    )
    (net (code "101") (name "N_VN") (class "Default")
      (node (ref "C31") (pin "1") (pinfunction "1_1") (pintype "passive"))
      (node (ref "C32") (pin "1") (pinfunction "1_1") (pintype "passive"))
      (node (ref "C33") (pin "1") (pinfunction "1_1") (pintype "passive"))
      (node (ref "C34") (pin "1") (pinfunction "1_1") (pintype "passive"))
      (node (ref "C35") (pin "1") (pinfunction "1_1") (pintype "passive"))
      (node (ref "C36") (pin "1") (pinfunction "1_1") (pintype "passive"))
      (node (ref "C37") (pin "1") (pinfunction "1_1") (pintype "passive"))
      (node (ref "C38") (pin "1") (pinfunction "1_1") (pintype "passive"))
      (node (ref "C39") (pin "1") (pinfunction "1_1") (pintype "passive"))
      (node (ref "C40") (pin "1") (pinfunction "1_1") (pintype "passive"))
      (node (ref "C41") (pin "1") (pinfunction "1_1") (pintype "passive"))
      (node (ref "C42") (pin "1") (pinfunction "1_1") (pintype "passive"))
      (node (ref "C43") (pin "1") (pinfunction "1_1") (pintype "passive"))
      (node (ref "C44") (pin "1") (pinfunction "1_1") (pintype "passive"))
      (node (ref "C68") (pin "1") (pinfunction "1_1") (pintype "passive"))
      (node (ref "C70") (pin "1") (pinfunction "1_1") (pintype "passive"))
      (node (ref "C78") (pin "1") (pinfunction "1_1") (pintype "passive"))
      (node (ref "C79") (pin "1") (pinfunction "1_1") (pintype "passive"))
      (node (ref "C80") (pin "1") (pinfunction "1_1") (pintype "passive"))
      (node (ref "C87") (pin "1") (pinfunction "1_1") (pintype "passive"))
      (node (ref "C88") (pin "1") (pinfunction "1_1") (pintype "passive"))
      (node (ref "C89") (pin "1") (pinfunction "1_1") (pintype "passive"))
      (node (ref "SENSOR") (pin "A10") (pinfunction "VDD18_A10") (pintype "power_in"))
      (node (ref "SENSOR") (pin "A15") (pinfunction "VDD18_A15") (pintype "power_in"))
      (node (ref "SENSOR") (pin "A16") (pinfunction "VDD18_A16") (pintype "power_in"))
      (node (ref "SENSOR") (pin "A22") (pinfunction "VDD18_A22") (pintype "power_in"))
      (node (ref "SENSOR") (pin "A26") (pinfunction "VDD18_A26") (pintype "power_in"))
      (node (ref "SENSOR") (pin "A27") (pinfunction "VDD18_A27") (pintype "power_in"))
      (node (ref "SENSOR") (pin "B4") (pinfunction "VDD18_B4") (pintype "power_in"))
      (node (ref "SENSOR") (pin "E1") (pinfunction "VDD18_PLL_E1") (pintype "power_in"))
      (node (ref "SENSOR") (pin "H10") (pinfunction "VDD18_H10") (pintype "power_in"))
      (node (ref "SENSOR") (pin "H15") (pinfunction "VDD18_H15") (pintype "power_in"))
      (node (ref "SENSOR") (pin "H16") (pinfunction "VDD18_H16") (pintype "power_in"))
      (node (ref "SENSOR") (pin "H22") (pinfunction "VDD18_H22") (pintype "power_in"))
      (node (ref "SENSOR") (pin "H26") (pinfunction "VDD18_H26") (pintype "power_in"))
      (node (ref "SENSOR") (pin "H5") (pinfunction "VDD18_H5") (pintype "power_in"))
      (node (ref "TP5") (pin "TP") (pinfunction "TP_TP") (pintype "input"))
      (node (ref "U5") (pin "14") (pinfunction "VCCA_14") (pintype "power_in"))
      (node (ref "U5") (pin "15") (pinfunction "DIR1_15") (pintype "input"))
      (node (ref "U5") (pin "16") (pinfunction "DIR2_16") (pintype "input"))
      (node (ref "U5") (pin "5") (pinfunction "DIR3_5") (pintype "input"))
      (node (ref "U6") (pin "14") (pinfunction "VCCA_14") (pintype "power_in"))
      (node (ref "U6") (pin "15") (pinfunction "DIR1_15") (pintype "input"))
      (node (ref "U6") (pin "5") (pinfunction "DIR3_5") (pintype "input"))
      (node (ref "U6") (pin "6") (pinfunction "DIR4_6") (pintype "input"))
      (node (ref "X-NORTH") (pin "49") (pinfunction "49_49") (pintype "bidirectional"))
      (node (ref "X-NORTH") (pin "55") (pinfunction "55_55") (pintype "bidirectional"))
      (node (ref "X-NORTH") (pin "61") (pinfunction "61_61") (pintype "bidirectional"))
      (node (ref "X-NORTH") (pin "67") (pinfunction "67_67") (pintype "bidirectional"))
      (node (ref "X-NORTH") (pin "73") (pinfunction "73_73") (pintype "bidirectional"))
      (node (ref "X-NORTH") (pin "79") (pinfunction "79_79") (pintype "bidirectional"))
      (node (ref "X-NORTH") (pin "85") (pinfunction "85_85") (pintype "bidirectional"))
      (node (ref "X-NORTH") (pin "91") (pinfunction "91_91") (pintype "bidirectional"))
      (node (ref "X-NORTH") (pin "97") (pinfunction "97_97") (pintype "bidirectional"))
    )
    (net (code "102") (name "N_VN_CV") (class "Default")
      (node (ref "C9") (pin "1") (pinfunction "1_1") (pintype "passive"))
      (node (ref "R4") (pin "1") (pinfunction "1_1") (pintype "passive"))
      (node (ref "X-NORTH") (pin "4") (pinfunction "4_4") (pintype "bidirectional"))
    )
    (net (code "103") (name "N_VN_OV") (class "Default")
      (node (ref "UNN") (pin "7") (pinfunction "OUTB_7") (pintype "output"))
      (node (ref "X-NORTH") (pin "3") (pinfunction "3_3") (pintype "bidirectional"))
    )
    (net (code "104") (name "N_VN_UV") (class "Default")
      (node (ref "UNN") (pin "1") (pinfunction "OUTA_1") (pintype "output"))
      (node (ref "X-NORTH") (pin "9") (pinfunction "9_9") (pintype "bidirectional"))
    )
    (net (code "105") (name "N_VW") (class "Default")
      (node (ref "C57") (pin "1") (pinfunction "1_1") (pintype "passive"))
      (node (ref "C58") (pin "1") (pinfunction "1_1") (pintype "passive"))
      (node (ref "C92") (pin "1") (pinfunction "1_1") (pintype "passive"))
      (node (ref "SENSOR") (pin "E2") (pinfunction "VDD_RES_E2") (pintype "power_in"))
      (node (ref "SENSOR") (pin "G4") (pinfunction "VDD_RES_G4") (pintype "power_in"))
      (node (ref "TP8") (pin "TP") (pinfunction "TP_TP") (pintype "input"))
      (node (ref "X-NORTH") (pin "13") (pinfunction "13_13") (pintype "bidirectional"))
      (node (ref "X-NORTH") (pin "19") (pinfunction "19_19") (pintype "bidirectional"))
      (node (ref "X-NORTH") (pin "25") (pinfunction "25_25") (pintype "bidirectional"))
      (node (ref "X-NORTH") (pin "31") (pinfunction "31_31") (pintype "bidirectional"))
      (node (ref "X-NORTH") (pin "37") (pinfunction "37_37") (pintype "bidirectional"))
    )
    (net (code "106") (name "N_VW_CV") (class "Default")
      (node (ref "C8") (pin "1") (pinfunction "1_1") (pintype "passive"))
      (node (ref "R1") (pin "1") (pinfunction "1_1") (pintype "passive"))
      (node (ref "X-NORTH") (pin "2") (pinfunction "2_2") (pintype "bidirectional"))
    )
    (net (code "107") (name "N_VW_OV") (class "Default")
      (node (ref "UNW") (pin "7") (pinfunction "OUTB_7") (pintype "output"))
      (node (ref "X-NORTH") (pin "1") (pinfunction "1_1") (pintype "bidirectional"))
    )
    (net (code "108") (name "N_VW_UV") (class "Default")
      (node (ref "UNW") (pin "1") (pinfunction "OUTA_1") (pintype "output"))
      (node (ref "X-NORTH") (pin "7") (pinfunction "7_7") (pintype "bidirectional"))
    )
    (net (code "109") (name "Net-(SENSORB-CMDN)") (class "Default")
      (node (ref "C61") (pin "1") (pinfunction "1_1") (pintype "passive"))
      (node (ref "SENSOR") (pin "F1") (pinfunction "CMDN_F1") (pintype "bidirectional"))
    )
    (net (code "110") (name "Net-(SENSORB-CMDP)") (class "Default")
      (node (ref "C22") (pin "2") (pinfunction "2_2") (pintype "passive"))
      (node (ref "SENSOR") (pin "F2") (pinfunction "CMDP_F2") (pintype "bidirectional"))
    )
    (net (code "111") (name "Net-(SENSORB-CMDP_COMP)") (class "Default")
      (node (ref "C28") (pin "2") (pinfunction "2_2") (pintype "passive"))
      (node (ref "SENSOR") (pin "H3") (pinfunction "CMDP_COMP_H3") (pintype "bidirectional"))
    )
    (net (code "112") (name "Net-(SENSORB-CMDP_COMP_INV)") (class "Default")
      (node (ref "C27") (pin "2") (pinfunction "2_2") (pintype "passive"))
      (node (ref "SENSOR") (pin "F3") (pinfunction "CMDP_COMP_INV_F3") (pintype "bidirectional"))
    )
    (net (code "113") (name "Net-(SENSORB-CMD_COLAMP)") (class "Default")
      (node (ref "C25") (pin "2") (pinfunction "2_2") (pintype "passive"))
      (node (ref "SENSOR") (pin "C6") (pinfunction "CMD_COLAMP_C6") (pintype "bidirectional"))
    )
    (net (code "114") (name "Net-(SENSORB-CMD_COL_LOAD)") (class "Default")
      (node (ref "C23") (pin "2") (pinfunction "2_2") (pintype "passive"))
      (node (ref "SENSOR") (pin "B1") (pinfunction "CMD_COL_LOAD_B1") (pintype "bidirectional"))
    )
    (net (code "115") (name "Net-(SENSORB-CMD_COL_PC)") (class "Default")
      (node (ref "C26") (pin "2") (pinfunction "2_2") (pintype "passive"))
      (node (ref "SENSOR") (pin "D1") (pinfunction "CMD_COL_PC_D1") (pintype "bidirectional"))
    )
    (net (code "116") (name "Net-(SENSORB-CMD_LVDS)") (class "Default")
      (node (ref "C62") (pin "1") (pinfunction "1_1") (pintype "passive"))
      (node (ref "SENSOR") (pin "C1") (pinfunction "CMD_LVDS_C1") (pintype "bidirectional"))
    )
    (net (code "117") (name "Net-(SENSORB-CMD_RAMP)") (class "Default")
      (node (ref "C24") (pin "2") (pinfunction "2_2") (pintype "passive"))
      (node (ref "SENSOR") (pin "B29") (pinfunction "CMD_RAMP_B29") (pintype "bidirectional"))
    )
    (net (code "118") (name "Net-(SENSORB-VBGAP)") (class "Default")
      (node (ref "C64") (pin "1") (pinfunction "1_1") (pintype "passive"))
      (node (ref "SENSOR") (pin "C29") (pinfunction "VBGAP_C29") (pintype "bidirectional"))
    )
    (net (code "119") (name "Net-(SENSORB-VCLAMP)") (class "Default")
      (node (ref "C63") (pin "1") (pinfunction "1_1") (pintype "passive"))
      (node (ref "SENSOR") (pin "D4") (pinfunction "VCLAMP_D4") (pintype "bidirectional"))
    )
    (net (code "120") (name "Net-(SENSORB-VCLAMP_ADC)") (class "Default")
      (node (ref "C60") (pin "1") (pinfunction "1_1") (pintype "passive"))
      (node (ref "SENSOR") (pin "G2") (pinfunction "VCLAMP_ADC_G2") (pintype "bidirectional"))
    )
    (net (code "121") (name "Net-(SENSORB-VPCH_H)") (class "Default")
      (node (ref "C71") (pin "1") (pinfunction "1_1") (pintype "passive"))
      (node (ref "SENSOR") (pin "C4") (pinfunction "VPCH_H_C4") (pintype "bidirectional"))
    )
    (net (code "122") (name "Net-(SENSORB-VPCH_L)") (class "Default")
      (node (ref "C14") (pin "1") (pinfunction "1_1") (pintype "passive"))
      (node (ref "SENSOR") (pin "A4") (pinfunction "VPCH_L_A4") (pintype "bidirectional"))
    )
    (net (code "123") (name "Net-(SENSORB-VREF)") (class "Default")
      (node (ref "C29") (pin "1") (pinfunction "1_1") (pintype "passive"))
      (node (ref "SENSOR") (pin "A3") (pinfunction "VREF_A3") (pintype "bidirectional"))
    )
    (net (code "124") (name "Net-(SENSORB-VREF_ADC)") (class "Default")
      (node (ref "C30") (pin "1") (pinfunction "1_1") (pintype "passive"))
      (node (ref "SENSOR") (pin "B3") (pinfunction "VREF_ADC_B3") (pintype "bidirectional"))
    )
    (net (code "125") (name "Net-(SENSORB-VRES_L)") (class "Default")
      (node (ref "C15") (pin "1") (pinfunction "1_1") (pintype "passive"))
      (node (ref "SENSOR") (pin "D5") (pinfunction "VRES_L_D5") (pintype "bidirectional"))
    )
    (net (code "126") (name "Net-(SENSORB-VTF_LOW0)") (class "Default")
      (node (ref "C18") (pin "1") (pinfunction "1_1") (pintype "passive"))
      (node (ref "SENSOR") (pin "C5") (pinfunction "VTF_LOW0_C5") (pintype "bidirectional"))
    )
    (net (code "127") (name "Net-(SENSORB-VTF_LOW1)") (class "Default")
      (node (ref "C19") (pin "1") (pinfunction "1_1") (pintype "passive"))
      (node (ref "SENSOR") (pin "D6") (pinfunction "VTF_LOW1_D6") (pintype "bidirectional"))
    )
    (net (code "128") (name "Net-(SENSORB-VTF_LOW2)") (class "Default")
      (node (ref "C20") (pin "1") (pinfunction "1_1") (pintype "passive"))
      (node (ref "SENSOR") (pin "B30") (pinfunction "VTF_LOW2_B30") (pintype "bidirectional"))
    )
    (net (code "129") (name "Net-(SENSORB-VTF_LOW3)") (class "Default")
      (node (ref "C21") (pin "1") (pinfunction "1_1") (pintype "passive"))
      (node (ref "SENSOR") (pin "C30") (pinfunction "VTF_LOW3_C30") (pintype "bidirectional"))
    )
    (net (code "130") (name "Net-(U3-ADJ)") (class "Default")
      (node (ref "R21") (pin "1") (pinfunction "1_1") (pintype "passive"))
      (node (ref "R22") (pin "2") (pinfunction "2_2") (pintype "passive"))
      (node (ref "U3") (pin "5") (pinfunction "ADJ_5") (pintype "input"))
    )
    (net (code "131") (name "Net-(U6-B4)") (class "Default")
      (node (ref "TP9") (pin "TP") (pinfunction "TP_TP") (pintype "input"))
      (node (ref "U6") (pin "9") (pinfunction "B4_9") (pintype "bidirectional"))
    )
    (net (code "132") (name "Net-(UEP-WP)") (class "Default")
      (node (ref "R1X") (pin "2") (pinfunction "2_2") (pintype "passive"))
      (node (ref "R2X") (pin "1") (pinfunction "1_1") (pintype "passive"))
      (node (ref "UEP") (pin "7") (pinfunction "WP_7") (pintype "input"))
    )
    (net (code "133") (name "Net-(UNE-VINA+)") (class "Default")
      (node (ref "R7") (pin "2") (pinfunction "2_2") (pintype "passive"))
      (node (ref "R8") (pin "1") (pinfunction "1_1") (pintype "passive"))
      (node (ref "UNE") (pin "3") (pinfunction "VINA+_3") (pintype "input"))
    )
    (net (code "134") (name "Net-(UNE-VINB-)") (class "Default")
      (node (ref "R8") (pin "2") (pinfunction "2_2") (pintype "passive"))
      (node (ref "R9") (pin "1") (pinfunction "1_1") (pintype "passive"))
      (node (ref "UNE") (pin "6") (pinfunction "VINB-_6") (pintype "input"))
    )
    (net (code "135") (name "Net-(UNN-VINA+)") (class "Default")
      (node (ref "R4") (pin "2") (pinfunction "2_2") (pintype "passive"))
      (node (ref "R5") (pin "1") (pinfunction "1_1") (pintype "passive"))
      (node (ref "UNN") (pin "3") (pinfunction "VINA+_3") (pintype "input"))
    )
    (net (code "136") (name "Net-(UNN-VINB-)") (class "Default")
      (node (ref "R5") (pin "2") (pinfunction "2_2") (pintype "passive"))
      (node (ref "R6") (pin "1") (pinfunction "1_1") (pintype "passive"))
      (node (ref "UNN") (pin "6") (pinfunction "VINB-_6") (pintype "input"))
    )
    (net (code "137") (name "Net-(UNW-VINA+)") (class "Default")
      (node (ref "R1") (pin "2") (pinfunction "2_2") (pintype "passive"))
      (node (ref "R2") (pin "1") (pinfunction "1_1") (pintype "passive"))
      (node (ref "UNW") (pin "3") (pinfunction "VINA+_3") (pintype "input"))
    )
    (net (code "138") (name "Net-(UNW-VINB-)") (class "Default")
      (node (ref "R2") (pin "2") (pinfunction "2_2") (pintype "passive"))
      (node (ref "R3") (pin "1") (pinfunction "1_1") (pintype "passive"))
      (node (ref "UNW") (pin "6") (pinfunction "VINB-_6") (pintype "input"))
    )
    (net (code "139") (name "Net-(USE-VINA+)") (class "Default")
      (node (ref "R10") (pin "2") (pinfunction "2_2") (pintype "passive"))
      (node (ref "R11") (pin "1") (pinfunction "1_1") (pintype "passive"))
      (node (ref "USE") (pin "3") (pinfunction "VINA+_3") (pintype "input"))
    )
    (net (code "140") (name "Net-(USE-VINB-)") (class "Default")
      (node (ref "R11") (pin "2") (pinfunction "2_2") (pintype "passive"))
      (node (ref "R12") (pin "1") (pinfunction "1_1") (pintype "passive"))
      (node (ref "USE") (pin "6") (pinfunction "VINB-_6") (pintype "input"))
    )
    (net (code "141") (name "Net-(USS-VINA+)") (class "Default")
      (node (ref "R13") (pin "2") (pinfunction "2_2") (pintype "passive"))
      (node (ref "R14") (pin "1") (pinfunction "1_1") (pintype "passive"))
      (node (ref "USS") (pin "3") (pinfunction "VINA+_3") (pintype "input"))
    )
    (net (code "142") (name "Net-(USS-VINB-)") (class "Default")
      (node (ref "R14") (pin "2") (pinfunction "2_2") (pintype "passive"))
      (node (ref "R15") (pin "1") (pinfunction "1_1") (pintype "passive"))
      (node (ref "USS") (pin "6") (pinfunction "VINB-_6") (pintype "input"))
    )
    (net (code "143") (name "Net-(USW-VINA+)") (class "Default")
      (node (ref "R16") (pin "2") (pinfunction "2_2") (pintype "passive"))
      (node (ref "R17") (pin "1") (pinfunction "1_1") (pintype "passive"))
      (node (ref "USW") (pin "3") (pinfunction "VINA+_3") (pintype "input"))
    )
    (net (code "144") (name "Net-(USW-VINB-)") (class "Default")
      (node (ref "R17") (pin "2") (pinfunction "2_2") (pintype "passive"))
      (node (ref "R18") (pin "1") (pinfunction "1_1") (pintype "passive"))
      (node (ref "USW") (pin "6") (pinfunction "VINB-_6") (pintype "input"))
    )
    (net (code "145") (name "S00_N") (class "Default")
      (node (ref "X-SOUTH") (pin "16") (pinfunction "16_16") (pintype "bidirectional"))
    )
    (net (code "146") (name "S00_P") (class "Default")
      (node (ref "X-SOUTH") (pin "14") (pinfunction "14_14") (pintype "bidirectional"))
    )
    (net (code "147") (name "S01_N") (class "Default")
      (node (ref "X-SOUTH") (pin "17") (pinfunction "17_17") (pintype "bidirectional"))
    )
    (net (code "148") (name "S01_P") (class "Default")
      (node (ref "X-SOUTH") (pin "15") (pinfunction "15_15") (pintype "bidirectional"))
    )
    (net (code "149") (name "S02_N") (class "Default")
      (node (ref "X-SOUTH") (pin "22") (pinfunction "22_22") (pintype "bidirectional"))
    )
    (net (code "150") (name "S02_P") (class "Default")
      (node (ref "X-SOUTH") (pin "20") (pinfunction "20_20") (pintype "bidirectional"))
    )
    (net (code "151") (name "S03_N") (class "Default")
      (node (ref "X-SOUTH") (pin "23") (pinfunction "23_23") (pintype "bidirectional"))
    )
    (net (code "152") (name "S03_P") (class "Default")
      (node (ref "X-SOUTH") (pin "21") (pinfunction "21_21") (pintype "bidirectional"))
    )
    (net (code "153") (name "S04_N") (class "Default")
      (node (ref "SENSOR") (pin "C24") (pinfunction "OUT32_N_C24") (pintype "output"))
      (node (ref "X-SOUTH") (pin "28") (pinfunction "28_28") (pintype "bidirectional"))
    )
    (net (code "154") (name "S04_P") (class "Default")
      (node (ref "SENSOR") (pin "C25") (pinfunction "OUT32_P_C25") (pintype "output"))
      (node (ref "X-SOUTH") (pin "26") (pinfunction "26_26") (pintype "bidirectional"))
    )
    (net (code "155") (name "S05_N") (class "Default")
      (node (ref "X-SOUTH") (pin "29") (pinfunction "29_29") (pintype "bidirectional"))
    )
    (net (code "156") (name "S05_P") (class "Default")
      (node (ref "X-SOUTH") (pin "27") (pinfunction "27_27") (pintype "bidirectional"))
    )
    (net (code "157") (name "S06_N") (class "Default")
      (node (ref "SENSOR") (pin "D23") (pinfunction "OUT30_N_D23") (pintype "output"))
      (node (ref "X-SOUTH") (pin "34") (pinfunction "34_34") (pintype "bidirectional"))
    )
    (net (code "158") (name "S06_P") (class "Default")
      (node (ref "SENSOR") (pin "D24") (pinfunction "OUT30_P_D24") (pintype "output"))
      (node (ref "X-SOUTH") (pin "32") (pinfunction "32_32") (pintype "bidirectional"))
    )
    (net (code "159") (name "S07_N") (class "Default")
      (node (ref "SENSOR") (pin "B24") (pinfunction "OUT31_N_B24") (pintype "output"))
      (node (ref "X-SOUTH") (pin "35") (pinfunction "35_35") (pintype "bidirectional"))
    )
    (net (code "160") (name "S07_P") (class "Default")
      (node (ref "SENSOR") (pin "B25") (pinfunction "OUT31_P_B25") (pintype "output"))
      (node (ref "X-SOUTH") (pin "33") (pinfunction "33_33") (pintype "bidirectional"))
    )
    (net (code "161") (name "S08_N") (class "Default")
      (node (ref "SENSOR") (pin "D21") (pinfunction "OUT27_N_D21") (pintype "output"))
      (node (ref "X-SOUTH") (pin "40") (pinfunction "40_40") (pintype "bidirectional"))
    )
    (net (code "162") (name "S08_P") (class "Default")
      (node (ref "SENSOR") (pin "D22") (pinfunction "OUT27_P_D22") (pintype "output"))
      (node (ref "X-SOUTH") (pin "38") (pinfunction "38_38") (pintype "bidirectional"))
    )
    (net (code "163") (name "S09_N") (class "Default")
      (node (ref "SENSOR") (pin "A23") (pinfunction "OUT29_N_A23") (pintype "output"))
      (node (ref "X-SOUTH") (pin "41") (pinfunction "41_41") (pintype "bidirectional"))
    )
    (net (code "164") (name "S09_P") (class "Default")
      (node (ref "SENSOR") (pin "A24") (pinfunction "OUT29_P_A24") (pintype "output"))
      (node (ref "X-SOUTH") (pin "39") (pinfunction "39_39") (pintype "bidirectional"))
    )
    (net (code "165") (name "S10_N") (class "Default")
      (node (ref "SENSOR") (pin "C21") (pinfunction "OUT28_N_C21") (pintype "output"))
      (node (ref "X-SOUTH") (pin "46") (pinfunction "46_46") (pintype "bidirectional"))
    )
    (net (code "166") (name "S10_P") (class "Default")
      (node (ref "SENSOR") (pin "C22") (pinfunction "OUT28_P_C22") (pintype "output"))
      (node (ref "X-SOUTH") (pin "44") (pinfunction "44_44") (pintype "bidirectional"))
    )
    (net (code "167") (name "S11_N") (class "Default")
      (node (ref "SENSOR") (pin "B20") (pinfunction "OUT26_N_B20") (pintype "output"))
      (node (ref "X-SOUTH") (pin "47") (pinfunction "47_47") (pintype "bidirectional"))
    )
    (net (code "168") (name "S11_P") (class "Default")
      (node (ref "SENSOR") (pin "B21") (pinfunction "OUT26_P_B21") (pintype "output"))
      (node (ref "X-SOUTH") (pin "45") (pinfunction "45_45") (pintype "bidirectional"))
    )
    (net (code "169") (name "S12_N") (class "Default")
      (node (ref "SENSOR") (pin "D19") (pinfunction "OUT24_N_D19") (pintype "output"))
      (node (ref "X-SOUTH") (pin "52") (pinfunction "52_52") (pintype "bidirectional"))
    )
    (net (code "170") (name "S12_P") (class "Default")
      (node (ref "SENSOR") (pin "D20") (pinfunction "OUT24_P_D20") (pintype "output"))
      (node (ref "X-SOUTH") (pin "50") (pinfunction "50_50") (pintype "bidirectional"))
    )
    (net (code "171") (name "S13_N") (class "Default")
      (node (ref "SENSOR") (pin "A19") (pinfunction "OUT23_N_A19") (pintype "output"))
      (node (ref "X-SOUTH") (pin "53") (pinfunction "53_53") (pintype "bidirectional"))
    )
    (net (code "172") (name "S13_P") (class "Default")
      (node (ref "SENSOR") (pin "A20") (pinfunction "OUT23_P_A20") (pintype "output"))
      (node (ref "X-SOUTH") (pin "51") (pinfunction "51_51") (pintype "bidirectional"))
    )
    (net (code "173") (name "S14_N") (class "Default")
      (node (ref "SENSOR") (pin "C19") (pinfunction "OUT25_N_C19") (pintype "output"))
      (node (ref "X-SOUTH") (pin "58") (pinfunction "58_58") (pintype "bidirectional"))
    )
    (net (code "174") (name "S14_P") (class "Default")
      (node (ref "SENSOR") (pin "C20") (pinfunction "OUT25_P_C20") (pintype "output"))
      (node (ref "X-SOUTH") (pin "56") (pinfunction "56_56") (pintype "bidirectional"))
    )
    (net (code "175") (name "S15_N") (class "Default")
      (node (ref "SENSOR") (pin "B18") (pinfunction "OUT22_N_B18") (pintype "output"))
      (node (ref "X-SOUTH") (pin "59") (pinfunction "59_59") (pintype "bidirectional"))
    )
    (net (code "176") (name "S15_P") (class "Default")
      (node (ref "SENSOR") (pin "B19") (pinfunction "OUT22_P_B19") (pintype "output"))
      (node (ref "X-SOUTH") (pin "57") (pinfunction "57_57") (pintype "bidirectional"))
    )
    (net (code "177") (name "S16_N") (class "Default")
      (node (ref "SENSOR") (pin "C17") (pinfunction "OUT21_N_C17") (pintype "output"))
      (node (ref "X-SOUTH") (pin "64") (pinfunction "64_64") (pintype "bidirectional"))
    )
    (net (code "178") (name "S16_P") (class "Default")
      (node (ref "SENSOR") (pin "C18") (pinfunction "OUT21_P_C18") (pintype "output"))
      (node (ref "X-SOUTH") (pin "62") (pinfunction "62_62") (pintype "bidirectional"))
    )
    (net (code "179") (name "S17_N") (class "Default")
      (node (ref "SENSOR") (pin "A17") (pinfunction "OUT19_N_A17") (pintype "output"))
      (node (ref "X-SOUTH") (pin "65") (pinfunction "65_65") (pintype "bidirectional"))
    )
    (net (code "180") (name "S17_P") (class "Default")
      (node (ref "SENSOR") (pin "A18") (pinfunction "OUT19_P_A18") (pintype "output"))
      (node (ref "X-SOUTH") (pin "63") (pinfunction "63_63") (pintype "bidirectional"))
    )
    (net (code "181") (name "S18_N") (class "Default")
      (node (ref "SENSOR") (pin "D17") (pinfunction "OUT20_N_D17") (pintype "output"))
      (node (ref "X-SOUTH") (pin "70") (pinfunction "70_70") (pintype "bidirectional"))
    )
    (net (code "182") (name "S18_P") (class "Default")
      (node (ref "SENSOR") (pin "D18") (pinfunction "OUT20_P_D18") (pintype "output"))
      (node (ref "X-SOUTH") (pin "68") (pinfunction "68_68") (pintype "bidirectional"))
    )
    (net (code "183") (name "S19_N") (class "Default")
      (node (ref "SENSOR") (pin "B16") (pinfunction "OUT18_N_B16") (pintype "output"))
      (node (ref "X-SOUTH") (pin "71") (pinfunction "71_71") (pintype "bidirectional"))
    )
    (net (code "184") (name "S19_P") (class "Default")
      (node (ref "SENSOR") (pin "B17") (pinfunction "OUT18_P_B17") (pintype "output"))
      (node (ref "X-SOUTH") (pin "69") (pinfunction "69_69") (pintype "bidirectional"))
    )
    (net (code "185") (name "S20_N") (class "Default")
      (node (ref "SENSOR") (pin "D15") (pinfunction "OUT17_N_D15") (pintype "output"))
      (node (ref "X-SOUTH") (pin "76") (pinfunction "76_76") (pintype "bidirectional"))
    )
    (net (code "186") (name "S20_P") (class "Default")
      (node (ref "SENSOR") (pin "D16") (pinfunction "OUT17_P_D16") (pintype "output"))
      (node (ref "X-SOUTH") (pin "74") (pinfunction "74_74") (pintype "bidirectional"))
    )
    (net (code "187") (name "S21_N") (class "Default")
      (node (ref "SENSOR") (pin "B14") (pinfunction "OUT16_N_B14") (pintype "output"))
      (node (ref "X-SOUTH") (pin "77") (pinfunction "77_77") (pintype "bidirectional"))
    )
    (net (code "188") (name "S21_P") (class "Default")
      (node (ref "SENSOR") (pin "B15") (pinfunction "OUT16_P_B15") (pintype "output"))
      (node (ref "X-SOUTH") (pin "75") (pinfunction "75_75") (pintype "bidirectional"))
    )
    (net (code "189") (name "S22_N") (class "Default")
      (node (ref "SENSOR") (pin "D13") (pinfunction "OUT15_N_D13") (pintype "output"))
      (node (ref "X-SOUTH") (pin "82") (pinfunction "82_82") (pintype "bidirectional"))
    )
    (net (code "190") (name "S22_P") (class "Default")
      (node (ref "SENSOR") (pin "D14") (pinfunction "OUT15_P_D14") (pintype "output"))
      (node (ref "X-SOUTH") (pin "80") (pinfunction "80_80") (pintype "bidirectional"))
    )
    (net (code "191") (name "S23_N") (class "Default")
      (node (ref "SENSOR") (pin "A13") (pinfunction "OUT13_N_A13") (pintype "output"))
      (node (ref "X-SOUTH") (pin "83") (pinfunction "83_83") (pintype "bidirectional"))
    )
    (net (code "192") (name "S23_P") (class "Default")
      (node (ref "SENSOR") (pin "A14") (pinfunction "OUT13_P_A14") (pintype "output"))
      (node (ref "X-SOUTH") (pin "81") (pinfunction "81_81") (pintype "bidirectional"))
    )
    (net (code "193") (name "S24_N") (class "Default")
      (node (ref "SENSOR") (pin "C13") (pinfunction "OUT14_N_C13") (pintype "output"))
      (node (ref "X-SOUTH") (pin "88") (pinfunction "88_88") (pintype "bidirectional"))
    )
    (net (code "194") (name "S24_P") (class "Default")
      (node (ref "SENSOR") (pin "C14") (pinfunction "OUT14_P_C14") (pintype "output"))
      (node (ref "X-SOUTH") (pin "86") (pinfunction "86_86") (pintype "bidirectional"))
    )
    (net (code "195") (name "S25_N") (class "Default")
      (node (ref "SENSOR") (pin "B12") (pinfunction "OUT12_N_B12") (pintype "output"))
      (node (ref "X-SOUTH") (pin "89") (pinfunction "89_89") (pintype "bidirectional"))
    )
    (net (code "196") (name "S25_P") (class "Default")
      (node (ref "SENSOR") (pin "B13") (pinfunction "OUT12_P_B13") (pintype "output"))
      (node (ref "X-SOUTH") (pin "87") (pinfunction "87_87") (pintype "bidirectional"))
    )
    (net (code "197") (name "S26_N") (class "Default")
      (node (ref "SENSOR") (pin "D11") (pinfunction "OUT10_N_D11") (pintype "output"))
      (node (ref "X-SOUTH") (pin "94") (pinfunction "94_94") (pintype "bidirectional"))
    )
    (net (code "198") (name "S26_P") (class "Default")
      (node (ref "SENSOR") (pin "D12") (pinfunction "OUT10_P_D12") (pintype "output"))
      (node (ref "X-SOUTH") (pin "92") (pinfunction "92_92") (pintype "bidirectional"))
    )
    (net (code "199") (name "S27_N") (class "Default")
      (node (ref "SENSOR") (pin "A11") (pinfunction "OUT9_N_A11") (pintype "output"))
      (node (ref "X-SOUTH") (pin "95") (pinfunction "95_95") (pintype "bidirectional"))
    )
    (net (code "200") (name "S27_P") (class "Default")
      (node (ref "SENSOR") (pin "A12") (pinfunction "OUT9_P_A12") (pintype "output"))
      (node (ref "X-SOUTH") (pin "93") (pinfunction "93_93") (pintype "bidirectional"))
    )
    (net (code "201") (name "S28_N") (class "Default")
      (node (ref "SENSOR") (pin "C11") (pinfunction "OUT11_N_C11") (pintype "output"))
      (node (ref "X-SOUTH") (pin "100") (pinfunction "100_100") (pintype "bidirectional"))
    )
    (net (code "202") (name "S28_P") (class "Default")
      (node (ref "SENSOR") (pin "C12") (pinfunction "OUT11_P_C12") (pintype "output"))
      (node (ref "X-SOUTH") (pin "98") (pinfunction "98_98") (pintype "bidirectional"))
    )
    (net (code "203") (name "S29_N") (class "Default")
      (node (ref "SENSOR") (pin "B10") (pinfunction "OUT8_N_B10") (pintype "output"))
      (node (ref "X-SOUTH") (pin "101") (pinfunction "101_101") (pintype "bidirectional"))
    )
    (net (code "204") (name "S29_P") (class "Default")
      (node (ref "SENSOR") (pin "B11") (pinfunction "OUT8_P_B11") (pintype "output"))
      (node (ref "X-SOUTH") (pin "99") (pinfunction "99_99") (pintype "bidirectional"))
    )
    (net (code "205") (name "S30_N") (class "Default")
      (node (ref "SENSOR") (pin "C9") (pinfunction "OUT7_N_C9") (pintype "output"))
      (node (ref "X-SOUTH") (pin "106") (pinfunction "106_106") (pintype "bidirectional"))
    )
    (net (code "206") (name "S30_P") (class "Default")
      (node (ref "SENSOR") (pin "C10") (pinfunction "OUT7_P_C10") (pintype "output"))
      (node (ref "X-SOUTH") (pin "104") (pinfunction "104_104") (pintype "bidirectional"))
    )
    (net (code "207") (name "S31_N") (class "Default")
      (node (ref "SENSOR") (pin "B8") (pinfunction "OUT5_N_B8") (pintype "output"))
      (node (ref "X-SOUTH") (pin "107") (pinfunction "107_107") (pintype "bidirectional"))
    )
    (net (code "208") (name "S31_P") (class "Default")
      (node (ref "SENSOR") (pin "B9") (pinfunction "OUT5_P_B9") (pintype "output"))
      (node (ref "X-SOUTH") (pin "105") (pinfunction "105_105") (pintype "bidirectional"))
    )
    (net (code "209") (name "S32_N") (class "Default")
      (node (ref "SENSOR") (pin "D9") (pinfunction "OUT6_N_D9") (pintype "output"))
      (node (ref "X-SOUTH") (pin "112") (pinfunction "112_112") (pintype "bidirectional"))
    )
    (net (code "210") (name "S32_P") (class "Default")
      (node (ref "SENSOR") (pin "D10") (pinfunction "OUT6_P_D10") (pintype "output"))
      (node (ref "X-SOUTH") (pin "110") (pinfunction "110_110") (pintype "bidirectional"))
    )
    (net (code "211") (name "S33_N") (class "Default")
      (node (ref "SENSOR") (pin "A7") (pinfunction "OUT2_N_A7") (pintype "output"))
      (node (ref "X-SOUTH") (pin "113") (pinfunction "113_113") (pintype "bidirectional"))
    )
    (net (code "212") (name "S33_P") (class "Default")
      (node (ref "SENSOR") (pin "A8") (pinfunction "OUT2_P_A8") (pintype "output"))
      (node (ref "X-SOUTH") (pin "111") (pinfunction "111_111") (pintype "bidirectional"))
    )
    (net (code "213") (name "S34_N") (class "Default")
      (node (ref "SENSOR") (pin "C7") (pinfunction "OUT4_N_C7") (pintype "output"))
      (node (ref "X-SOUTH") (pin "118") (pinfunction "118_118") (pintype "bidirectional"))
    )
    (net (code "214") (name "S34_P") (class "Default")
      (node (ref "SENSOR") (pin "C8") (pinfunction "OUT4_P_C8") (pintype "output"))
      (node (ref "X-SOUTH") (pin "116") (pinfunction "116_116") (pintype "bidirectional"))
    )
    (net (code "215") (name "S35_N") (class "Default")
      (node (ref "SENSOR") (pin "B6") (pinfunction "OUT1_N_B6") (pintype "output"))
      (node (ref "X-SOUTH") (pin "119") (pinfunction "119_119") (pintype "bidirectional"))
    )
    (net (code "216") (name "S35_P") (class "Default")
      (node (ref "SENSOR") (pin "B7") (pinfunction "OUT1_P_B7") (pintype "output"))
      (node (ref "X-SOUTH") (pin "117") (pinfunction "117_117") (pintype "bidirectional"))
    )
    (net (code "217") (name "S36_N") (class "Default")
      (node (ref "SENSOR") (pin "D7") (pinfunction "OUT3_N_D7") (pintype "output"))
      (node (ref "X-SOUTH") (pin "124") (pinfunction "124_124") (pintype "bidirectional"))
    )
    (net (code "218") (name "S36_P") (class "Default")
      (node (ref "SENSOR") (pin "D8") (pinfunction "OUT3_P_D8") (pintype "output"))
      (node (ref "X-SOUTH") (pin "122") (pinfunction "122_122") (pintype "bidirectional"))
    )
    (net (code "219") (name "S37_N") (class "Default")
      (node (ref "SENSOR") (pin "A5") (pinfunction "OUTCTR_N_A5") (pintype "output"))
      (node (ref "X-SOUTH") (pin "125") (pinfunction "125_125") (pintype "bidirectional"))
    )
    (net (code "220") (name "S37_P") (class "Default")
      (node (ref "SENSOR") (pin "A6") (pinfunction "OUTCTR_P_A6") (pintype "output"))
      (node (ref "X-SOUTH") (pin "123") (pinfunction "123_123") (pintype "bidirectional"))
    )
    (net (code "221") (name "S38_N") (class "Default")
      (node (ref "X-SOUTH") (pin "130") (pinfunction "130_130") (pintype "bidirectional"))
    )
    (net (code "222") (name "S38_P") (class "Default")
      (node (ref "X-SOUTH") (pin "128") (pinfunction "128_128") (pintype "bidirectional"))
    )
    (net (code "223") (name "S39_N") (class "Default")
      (node (ref "U3") (pin "6") (pinfunction "EN_6") (pintype "input"))
      (node (ref "X-SOUTH") (pin "131") (pinfunction "131_131") (pintype "bidirectional"))
    )
    (net (code "224") (name "S39_P") (class "Default")
      (node (ref "X-SOUTH") (pin "129") (pinfunction "129_129") (pintype "bidirectional"))
    )
    (net (code "225") (name "SPI_CLK") (class "Default")
      (node (ref "SENSOR") (pin "H29") (pinfunction "SPI_CLK_H29") (pintype "input"))
      (node (ref "U4") (pin "9") (pinfunction "B4_9") (pintype "bidirectional"))
    )
    (net (code "226") (name "SPI_EN") (class "Default")
      (node (ref "SENSOR") (pin "F28") (pinfunction "SPI_EN_F28") (pintype "input"))
      (node (ref "U4") (pin "12") (pinfunction "B1_12") (pintype "bidirectional"))
    )
    (net (code "227") (name "SPI_IN") (class "Default")
      (node (ref "SENSOR") (pin "E28") (pinfunction "SPI_IN_E28") (pintype "input"))
      (node (ref "U4") (pin "10") (pinfunction "B3_10") (pintype "bidirectional"))
    )
    (net (code "228") (name "SPI_OUT") (class "Default")
      (node (ref "SENSOR") (pin "G28") (pinfunction "SPI_OUT_G28") (pintype "output"))
      (node (ref "U4") (pin "11") (pinfunction "B2_11") (pintype "bidirectional"))
    )
    (net (code "229") (name "SYS_RES_N") (class "Default")
      (node (ref "SENSOR") (pin "F30") (pinfunction "SYS_RES_N_F30") (pintype "input"))
      (node (ref "U5") (pin "10") (pinfunction "B3_10") (pintype "bidirectional"))
    )
    (net (code "230") (name "S_CHK_EN") (class "Default")
      (node (ref "X-SOUTH") (pin "8") (pinfunction "8_8") (pintype "bidirectional"))
    )
    (net (code "231") (name "S_CHK_V") (class "Default")
      (node (ref "C5") (pin "1") (pinfunction "1_1") (pintype "passive"))
      (node (ref "C6") (pin "1") (pinfunction "1_1") (pintype "passive"))
      (node (ref "C7") (pin "1") (pinfunction "1_1") (pintype "passive"))
      (node (ref "R20") (pin "1") (pinfunction "1_1") (pintype "passive"))
      (node (ref "TP3") (pin "TP") (pinfunction "TP_TP") (pintype "input"))
      (node (ref "USE") (pin "8") (pinfunction "VDD_8") (pintype "power_in"))
      (node (ref "USS") (pin "8") (pinfunction "VDD_8") (pintype "power_in"))
      (node (ref "USW") (pin "8") (pinfunction "VDD_8") (pintype "power_in"))
      (node (ref "X-SOUTH") (pin "10") (pinfunction "10_10") (pintype "bidirectional"))
    )
    (net (code "232") (name "S_I2C_EN") (class "Default")
      (node (ref "X-SOUTH") (pin "137") (pinfunction "137_137") (pintype "bidirectional"))
    )
    (net (code "233") (name "S_I2C_V") (class "Default")
      (node (ref "U7") (pin "8") (pinfunction "VCC_8") (pintype "power_in"))
      (node (ref "X-SOUTH") (pin "135") (pinfunction "135_135") (pintype "bidirectional"))
    )
    (net (code "234") (name "S_REF") (class "Default")
      (node (ref "R20") (pin "2") (pinfunction "2_2") (pintype "passive"))
      (node (ref "TP4") (pin "TP") (pinfunction "TP_TP") (pintype "input"))
      (node (ref "U2") (pin "1") (pinfunction "CATHODE_1") (pintype "output"))
      (node (ref "U2") (pin "3") (pinfunction "REF_3") (pintype "input"))
      (node (ref "USE") (pin "2") (pinfunction "VINA-_2") (pintype "input"))
      (node (ref "USE") (pin "5") (pinfunction "VINB+_5") (pintype "input"))
      (node (ref "USS") (pin "2") (pinfunction "VINA-_2") (pintype "input"))
      (node (ref "USS") (pin "5") (pinfunction "VINB+_5") (pintype "input"))
      (node (ref "USW") (pin "2") (pinfunction "VINA-_2") (pintype "input"))
      (node (ref "USW") (pin "5") (pinfunction "VINB+_5") (pintype "input"))
    )
    (net (code "235") (name "S_SCK") (class "Default")
      (node (ref "X-SOUTH") (pin "144") (pinfunction "144_144") (pintype "bidirectional"))
    )
    (net (code "236") (name "S_SCL") (class "Default")
      (node (ref "U7") (pin "2") (pinfunction "SCL_2") (pintype "input"))
      (node (ref "X-SOUTH") (pin "143") (pinfunction "143_143") (pintype "bidirectional"))
    )
    (net (code "237") (name "S_SDA") (class "Default")
      (node (ref "U7") (pin "1") (pinfunction "SDA_1") (pintype "bidirectional"))
      (node (ref "X-SOUTH") (pin "141") (pinfunction "141_141") (pintype "bidirectional"))
    )
    (net (code "238") (name "S_SDI") (class "Default")
      (node (ref "X-SOUTH") (pin "140") (pinfunction "140_140") (pintype "bidirectional"))
    )
    (net (code "239") (name "S_SDO") (class "Default")
      (node (ref "X-SOUTH") (pin "142") (pinfunction "142_142") (pintype "bidirectional"))
    )
    (net (code "240") (name "S_SPI_EN") (class "Default")
      (node (ref "X-SOUTH") (pin "136") (pinfunction "136_136") (pintype "bidirectional"))
    )
    (net (code "241") (name "S_SPI_V") (class "Default")
      (node (ref "X-SOUTH") (pin "134") (pinfunction "134_134") (pintype "bidirectional"))
    )
    (net (code "242") (name "S_VE") (class "Default")
      (node (ref "X-SOUTH") (pin "13") (pinfunction "13_13") (pintype "bidirectional"))
      (node (ref "X-SOUTH") (pin "19") (pinfunction "19_19") (pintype "bidirectional"))
      (node (ref "X-SOUTH") (pin "25") (pinfunction "25_25") (pintype "bidirectional"))
      (node (ref "X-SOUTH") (pin "31") (pinfunction "31_31") (pintype "bidirectional"))
      (node (ref "X-SOUTH") (pin "37") (pinfunction "37_37") (pintype "bidirectional"))
    )
    (net (code "243") (name "S_VE_CV") (class "Default")
      (node (ref "C11") (pin "1") (pinfunction "1_1") (pintype "passive"))
      (node (ref "R10") (pin "1") (pinfunction "1_1") (pintype "passive"))
      (node (ref "X-SOUTH") (pin "2") (pinfunction "2_2") (pintype "bidirectional"))
    )
    (net (code "244") (name "S_VE_OV") (class "Default")
      (node (ref "USE") (pin "7") (pinfunction "OUTB_7") (pintype "output"))
      (node (ref "X-SOUTH") (pin "1") (pinfunction "1_1") (pintype "bidirectional"))
    )
    (net (code "245") (name "S_VE_UV") (class "Default")
      (node (ref "USE") (pin "1") (pinfunction "OUTA_1") (pintype "output"))
      (node (ref "X-SOUTH") (pin "7") (pinfunction "7_7") (pintype "bidirectional"))
    )
    (net (code "246") (name "S_VS") (class "Default")
      (node (ref "C45") (pin "1") (pinfunction "1_1") (pintype "passive"))
      (node (ref "C46") (pin "1") (pinfunction "1_1") (pintype "passive"))
      (node (ref "C47") (pin "1") (pinfunction "1_1") (pintype "passive"))
      (node (ref "C48") (pin "1") (pinfunction "1_1") (pintype "passive"))
      (node (ref "C49") (pin "1") (pinfunction "1_1") (pintype "passive"))
      (node (ref "C72") (pin "1") (pinfunction "1_1") (pintype "passive"))
      (node (ref "C73") (pin "1") (pinfunction "1_1") (pintype "passive"))
      (node (ref "C74") (pin "1") (pinfunction "1_1") (pintype "passive"))
      (node (ref "C81") (pin "1") (pinfunction "1_1") (pintype "passive"))
      (node (ref "C82") (pin "1") (pinfunction "1_1") (pintype "passive"))
      (node (ref "C83") (pin "1") (pinfunction "1_1") (pintype "passive"))
      (node (ref "SENSOR") (pin "A30") (pinfunction "VDD_PIX_A30") (pintype "power_in"))
      (node (ref "SENSOR") (pin "D28") (pinfunction "VDD_PIX_D28") (pintype "power_in"))
      (node (ref "SENSOR") (pin "D30") (pinfunction "VDD_PIX_D30") (pintype "power_in"))
      (node (ref "SENSOR") (pin "G1") (pinfunction "VDD_PIX_G1") (pintype "power_in"))
      (node (ref "SENSOR") (pin "H28") (pinfunction "VDD_PIX_H28") (pintype "power_in"))
      (node (ref "TP6") (pin "TP") (pinfunction "TP_TP") (pintype "input"))
      (node (ref "X-SOUTH") (pin "49") (pinfunction "49_49") (pintype "bidirectional"))
      (node (ref "X-SOUTH") (pin "55") (pinfunction "55_55") (pintype "bidirectional"))
      (node (ref "X-SOUTH") (pin "61") (pinfunction "61_61") (pintype "bidirectional"))
      (node (ref "X-SOUTH") (pin "67") (pinfunction "67_67") (pintype "bidirectional"))
      (node (ref "X-SOUTH") (pin "73") (pinfunction "73_73") (pintype "bidirectional"))
      (node (ref "X-SOUTH") (pin "79") (pinfunction "79_79") (pintype "bidirectional"))
      (node (ref "X-SOUTH") (pin "85") (pinfunction "85_85") (pintype "bidirectional"))
      (node (ref "X-SOUTH") (pin "91") (pinfunction "91_91") (pintype "bidirectional"))
      (node (ref "X-SOUTH") (pin "97") (pinfunction "97_97") (pintype "bidirectional"))
    )
    (net (code "247") (name "S_VS_CV") (class "Default")
      (node (ref "C12") (pin "1") (pinfunction "1_1") (pintype "passive"))
      (node (ref "R13") (pin "1") (pinfunction "1_1") (pintype "passive"))
      (node (ref "X-SOUTH") (pin "4") (pinfunction "4_4") (pintype "bidirectional"))
    )
    (net (code "248") (name "S_VS_OV") (class "Default")
      (node (ref "USS") (pin "7") (pinfunction "OUTB_7") (pintype "output"))
      (node (ref "X-SOUTH") (pin "3") (pinfunction "3_3") (pintype "bidirectional"))
    )
    (net (code "249") (name "S_VS_UV") (class "Default")
      (node (ref "USS") (pin "1") (pinfunction "OUTA_1") (pintype "output"))
      (node (ref "X-SOUTH") (pin "9") (pinfunction "9_9") (pintype "bidirectional"))
    )
    (net (code "250") (name "S_VW") (class "Default")
      (node (ref "C90") (pin "1") (pinfunction "1_1") (pintype "passive"))
      (node (ref "U3") (pin "1") (pinfunction "BIAS_1") (pintype "power_in"))
      (node (ref "U3") (pin "3") (pinfunction "IN_3") (pintype "power_in"))
      (node (ref "X-SOUTH") (pin "109") (pinfunction "109_109") (pintype "bidirectional"))
      (node (ref "X-SOUTH") (pin "115") (pinfunction "115_115") (pintype "bidirectional"))
      (node (ref "X-SOUTH") (pin "121") (pinfunction "121_121") (pintype "bidirectional"))
      (node (ref "X-SOUTH") (pin "127") (pinfunction "127_127") (pintype "bidirectional"))
      (node (ref "X-SOUTH") (pin "133") (pinfunction "133_133") (pintype "bidirectional"))
    )
    (net (code "251") (name "S_VW_CV") (class "Default")
      (node (ref "C13") (pin "1") (pinfunction "1_1") (pintype "passive"))
      (node (ref "R16") (pin "1") (pinfunction "1_1") (pintype "passive"))
      (node (ref "X-SOUTH") (pin "6") (pinfunction "6_6") (pintype "bidirectional"))
    )
    (net (code "252") (name "S_VW_OV") (class "Default")
      (node (ref "USW") (pin "7") (pinfunction "OUTB_7") (pintype "output"))
      (node (ref "X-SOUTH") (pin "5") (pinfunction "5_5") (pintype "bidirectional"))
    )
    (net (code "253") (name "S_VW_UV") (class "Default")
      (node (ref "USW") (pin "1") (pinfunction "OUTA_1") (pintype "output"))
      (node (ref "X-SOUTH") (pin "11") (pinfunction "11_11") (pintype "bidirectional"))
    )
    (net (code "254") (name "TDIG1") (class "Default")
      (node (ref "SENSOR") (pin "G27") (pinfunction "TDIG1_G27") (pintype "output"))
      (node (ref "U5") (pin "9") (pinfunction "B4_9") (pintype "bidirectional"))
    )
    (net (code "255") (name "TDIG2") (class "Default")
      (node (ref "SENSOR") (pin "G26") (pinfunction "TDIG2_G26") (pintype "output"))
      (node (ref "U6") (pin "11") (pinfunction "B2_11") (pintype "bidirectional"))
    )
    (net (code "256") (name "T_EXP1") (class "Default")
      (node (ref "SENSOR") (pin "H30") (pinfunction "T_EXP1_H30") (pintype "input"))
      (node (ref "U5") (pin "12") (pinfunction "B1_12") (pintype "bidirectional"))
    )
    (net (code "257") (name "T_EXP2") (class "Default")
      (node (ref "SENSOR") (pin "E29") (pinfunction "T_EXP2_E29") (pintype "input"))
      (node (ref "U6") (pin "10") (pinfunction "B3_10") (pintype "bidirectional"))
    )
    (net (code "258") (name "VRAMP1") (class "Default")
      (node (ref "C16") (pin "1") (pinfunction "1_1") (pintype "passive"))
      (node (ref "R23") (pin "1") (pinfunction "1_1") (pintype "passive"))
      (node (ref "SENSOR") (pin "G29") (pinfunction "VRAMP1_G29") (pintype "bidirectional"))
    )
    (net (code "259") (name "VRAMP2") (class "Default")
      (node (ref "C17") (pin "1") (pinfunction "1_1") (pintype "passive"))
      (node (ref "R23") (pin "2") (pinfunction "2_2") (pintype "passive"))
      (node (ref "SENSOR") (pin "F29") (pinfunction "VRAMP2_F29") (pintype "bidirectional"))
    )
    (net (code "260") (name "VTREF") (class "Default")
      (node (ref "C65") (pin "1") (pinfunction "1_1") (pintype "passive"))
      (node (ref "C91") (pin "2") (pinfunction "2_2") (pintype "passive"))
      (node (ref "R21") (pin "2") (pinfunction "2_2") (pintype "passive"))
      (node (ref "R24") (pin "1") (pinfunction "1_1") (pintype "passive"))
      (node (ref "SENSOR") (pin "B2") (pinfunction "VTREF_B2") (pintype "bidirectional"))
      (node (ref "U3") (pin "4") (pinfunction "OUT_4") (pintype "power_in"))
    )
    (net (code "261") (name "VTSIG") (class "Default")
      (node (ref "C66") (pin "1") (pinfunction "1_1") (pintype "passive"))
      (node (ref "R24") (pin "2") (pinfunction "2_2") (pintype "passive"))
      (node (ref "SENSOR") (pin "C2") (pinfunction "VTSIG_C2") (pintype "bidirectional"))
    )
    (net (code "262") (name "unconnected-(U1-NC-Pad2)") (class "Default")
      (node (ref "U1") (pin "2") (pinfunction "NC_2") (pintype "no_connect"))
    )
    (net (code "263") (name "unconnected-(U1-NC-Pad4)") (class "Default")
      (node (ref "U1") (pin "4") (pinfunction "NC_4") (pintype "no_connect"))
    )
    (net (code "264") (name "unconnected-(U1-NC-Pad5)") (class "Default")
      (node (ref "U1") (pin "5") (pinfunction "NC_5") (pintype "no_connect"))
    )
    (net (code "265") (name "unconnected-(U2-NC-Pad2)") (class "Default")
      (node (ref "U2") (pin "2") (pinfunction "NC_2") (pintype "no_connect"))
    )
    (net (code "266") (name "unconnected-(U2-NC-Pad4)") (class "Default")
      (node (ref "U2") (pin "4") (pinfunction "NC_4") (pintype "no_connect"))
    )
    (net (code "267") (name "unconnected-(U2-NC-Pad5)") (class "Default")
      (node (ref "U2") (pin "5") (pinfunction "NC_5") (pintype "no_connect"))
    )
    (net (code "268") (name "unconnected-(U7-OS-Pad3)") (class "Default")
      (node (ref "U7") (pin "3") (pinfunction "OS_3") (pintype "output"))
    )
    (net (code "269") (name "unconnected-(X-NORTH-PadM1)") (class "Default")
      (node (ref "X-NORTH") (pin "M1") (pinfunction "M1_M1") (pintype "bidirectional"))
    )
    (net (code "270") (name "unconnected-(X-NORTH-PadM2)") (class "Default")
      (node (ref "X-NORTH") (pin "M2") (pinfunction "M2_M2") (pintype "bidirectional"))
    )
    (net (code "271") (name "unconnected-(X-SOUTH-PadM1)") (class "Default")
      (node (ref "X-SOUTH") (pin "M1") (pinfunction "M1_M1") (pintype "bidirectional"))
    )
    (net (code "272") (name "unconnected-(X-SOUTH-PadM2)") (class "Default")
      (node (ref "X-SOUTH") (pin "M2") (pinfunction "M2_M2") (pintype "bidirectional"))
    )
  )
)
